# CNC.net
KiCad netlist of a schematic drawn in EAGLE
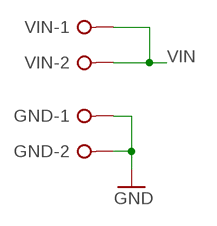
[diagram p0: schematic, sheet 1, part 1 of 2]
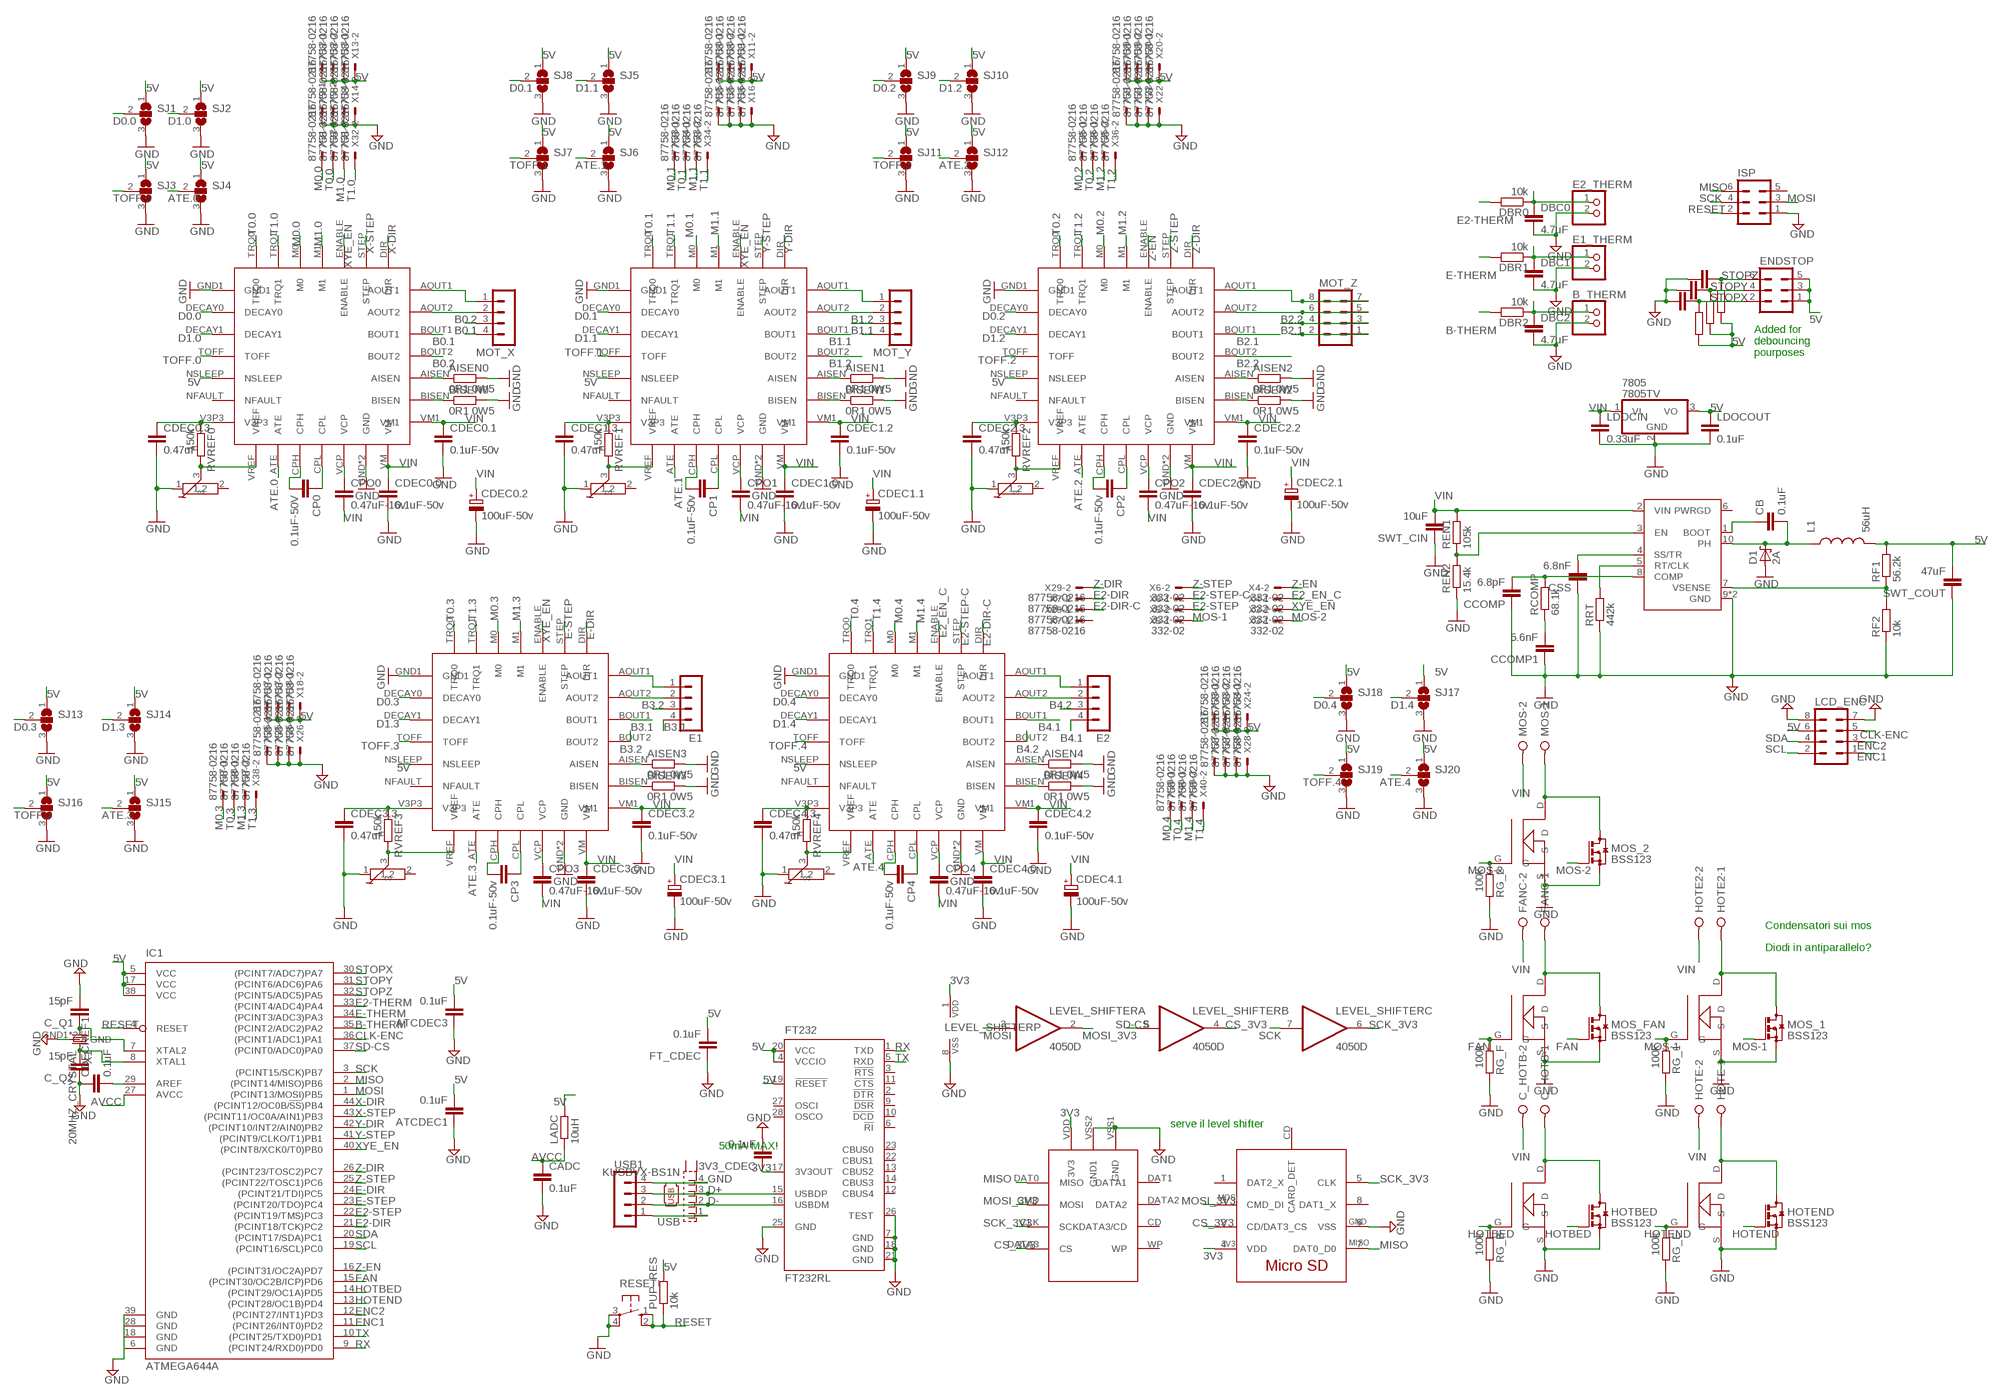
[diagram p1: schematic, sheet 1, part 2 of 2]

(export (version "E")
  (design (tool "Eeschema 10.0.6"))
  (components
    (comp (ref "3V3_CDEC")
      (value "0.1uF")
      (footprint "eagle-import:C0603")
      (libsource (lib "eagle-import") (part "C-EUC0603"))
    )
    (comp (ref "7805")
      (value "7805TV")
      (footprint "eagle-import:TO220V")
      (libsource (lib "eagle-import") (part "78TV05"))
    )
    (comp (ref "AISEN0")
      (value "0R1 0W5")
      (footprint "eagle-import:R0805")
      (libsource (lib "eagle-import") (part "R-EU_R0805"))
    )
    (comp (ref "AISEN1")
      (value "0R1 0W5")
      (footprint "eagle-import:R0805")
      (libsource (lib "eagle-import") (part "R-EU_R0805"))
    )
    (comp (ref "AISEN2")
      (value "0R1 0W5")
      (footprint "eagle-import:R0805")
      (libsource (lib "eagle-import") (part "R-EU_R0805"))
    )
    (comp (ref "AISEN3")
      (value "0R1 0W5")
      (footprint "eagle-import:R0805")
      (libsource (lib "eagle-import") (part "R-EU_R0805"))
    )
    (comp (ref "AISEN4")
      (value "0R1 0W5")
      (footprint "eagle-import:R0805")
      (libsource (lib "eagle-import") (part "R-EU_R0805"))
    )
    (comp (ref "ATCDEC1")
      (value "0.1uF")
      (footprint "eagle-import:C0603")
      (libsource (lib "eagle-import") (part "C-EUC0603"))
    )
    (comp (ref "ATCDEC3")
      (value "0.1uF")
      (footprint "eagle-import:C0603")
      (libsource (lib "eagle-import") (part "C-EUC0603"))
    )
    (comp (ref "BISEN0")
      (value "0R1 0W5")
      (footprint "eagle-import:R0805")
      (libsource (lib "eagle-import") (part "R-EU_R0805"))
    )
    (comp (ref "BISEN1")
      (value "0R1 0W5")
      (footprint "eagle-import:R0805")
      (libsource (lib "eagle-import") (part "R-EU_R0805"))
    )
    (comp (ref "BISEN2")
      (value "0R1 0W5")
      (footprint "eagle-import:R0805")
      (libsource (lib "eagle-import") (part "R-EU_R0805"))
    )
    (comp (ref "BISEN3")
      (value "0R1 0W5")
      (footprint "eagle-import:R0805")
      (libsource (lib "eagle-import") (part "R-EU_R0805"))
    )
    (comp (ref "BISEN4")
      (value "0R1 0W5")
      (footprint "eagle-import:R0805")
      (libsource (lib "eagle-import") (part "R-EU_R0805"))
    )
    (comp (ref "B_THERM")
      (value "PINHD-1X2")
      (footprint "eagle-import:1X02")
      (libsource (lib "eagle-import") (part "PINHD-1X2"))
    )
    (comp (ref "CADC")
      (value "0.1uF")
      (footprint "eagle-import:C0603")
      (libsource (lib "eagle-import") (part "C-EUC0603"))
    )
    (comp (ref "CB")
      (value "0.1uF")
      (footprint "eagle-import:C0603")
      (libsource (lib "eagle-import") (part "C-EUC0603"))
    )
    (comp (ref "CCOMP")
      (value "6.8pF")
      (footprint "eagle-import:C0603")
      (libsource (lib "eagle-import") (part "C-EUC0603"))
    )
    (comp (ref "CCOMP1")
      (value "5.6nF")
      (footprint "eagle-import:C0603")
      (libsource (lib "eagle-import") (part "C-EUC0603"))
    )
    (comp (ref "CDEC0.0")
      (value "0.1uF-50v")
      (footprint "eagle-import:C0603")
      (libsource (lib "eagle-import") (part "C-EUC0603"))
    )
    (comp (ref "CDEC0.1")
      (value "0.1uF-50v")
      (footprint "eagle-import:C0603")
      (libsource (lib "eagle-import") (part "C-EUC0603"))
    )
    (comp (ref "CDEC0.2")
      (value "100uF-50v")
      (footprint "eagle-import:E3,5-8")
      (libsource (lib "eagle-import") (part "CPOL-EUE3.5-8"))
    )
    (comp (ref "CDEC0.3")
      (value "0.47uF")
      (footprint "eagle-import:C0603")
      (libsource (lib "eagle-import") (part "C-EUC0603"))
    )
    (comp (ref "CDEC1.0")
      (value "0.1uF-50v")
      (footprint "eagle-import:C0603")
      (libsource (lib "eagle-import") (part "C-EUC0603"))
    )
    (comp (ref "CDEC1.1")
      (value "100uF-50v")
      (footprint "eagle-import:E3,5-8")
      (libsource (lib "eagle-import") (part "CPOL-EUE3.5-8"))
    )
    (comp (ref "CDEC1.2")
      (value "0.1uF-50v")
      (footprint "eagle-import:C0603")
      (libsource (lib "eagle-import") (part "C-EUC0603"))
    )
    (comp (ref "CDEC1.3")
      (value "0.47uF")
      (footprint "eagle-import:C0603")
      (libsource (lib "eagle-import") (part "C-EUC0603"))
    )
    (comp (ref "CDEC2.0")
      (value "0.1uF-50v")
      (footprint "eagle-import:C0603")
      (libsource (lib "eagle-import") (part "C-EUC0603"))
    )
    (comp (ref "CDEC2.1")
      (value "100uF-50v")
      (footprint "eagle-import:E3,5-8")
      (libsource (lib "eagle-import") (part "CPOL-EUE3.5-8"))
    )
    (comp (ref "CDEC2.2")
      (value "0.1uF-50v")
      (footprint "eagle-import:C0603")
      (libsource (lib "eagle-import") (part "C-EUC0603"))
    )
    (comp (ref "CDEC2.3")
      (value "0.47uF")
      (footprint "eagle-import:C0603")
      (libsource (lib "eagle-import") (part "C-EUC0603"))
    )
    (comp (ref "CDEC3.0")
      (value "0.1uF-50v")
      (footprint "eagle-import:C0603")
      (libsource (lib "eagle-import") (part "C-EUC0603"))
    )
    (comp (ref "CDEC3.1")
      (value "100uF-50v")
      (footprint "eagle-import:E3,5-8")
      (libsource (lib "eagle-import") (part "CPOL-EUE3.5-8"))
    )
    (comp (ref "CDEC3.2")
      (value "0.1uF-50v")
      (footprint "eagle-import:C0603")
      (libsource (lib "eagle-import") (part "C-EUC0603"))
    )
    (comp (ref "CDEC3.3")
      (value "0.47uF")
      (footprint "eagle-import:C0603")
      (libsource (lib "eagle-import") (part "C-EUC0603"))
    )
    (comp (ref "CDEC4.0")
      (value "0.1uF-50v")
      (footprint "eagle-import:C0603")
      (libsource (lib "eagle-import") (part "C-EUC0603"))
    )
    (comp (ref "CDEC4.1")
      (value "100uF-50v")
      (footprint "eagle-import:E3,5-8")
      (libsource (lib "eagle-import") (part "CPOL-EUE3.5-8"))
    )
    (comp (ref "CDEC4.2")
      (value "0.1uF-50v")
      (footprint "eagle-import:C0603")
      (libsource (lib "eagle-import") (part "C-EUC0603"))
    )
    (comp (ref "CDEC4.3")
      (value "0.47uF")
      (footprint "eagle-import:C0603")
      (libsource (lib "eagle-import") (part "C-EUC0603"))
    )
    (comp (ref "CDECREF1")
      (value "0.1uF")
      (footprint "eagle-import:C0603")
      (libsource (lib "eagle-import") (part "C-EUC0603"))
    )
    (comp (ref "CP0")
      (value "0.1uF-50V")
      (footprint "eagle-import:C0603")
      (libsource (lib "eagle-import") (part "C-EUC0603"))
    )
    (comp (ref "CP1")
      (value "0.1uF-50v")
      (footprint "eagle-import:C0603")
      (libsource (lib "eagle-import") (part "C-EUC0603"))
    )
    (comp (ref "CP2")
      (value "0.1uF-50v")
      (footprint "eagle-import:C0603")
      (libsource (lib "eagle-import") (part "C-EUC0603"))
    )
    (comp (ref "CP3")
      (value "0.1uF-50v")
      (footprint "eagle-import:C0603")
      (libsource (lib "eagle-import") (part "C-EUC0603"))
    )
    (comp (ref "CP4")
      (value "0.1uF-50v")
      (footprint "eagle-import:C0603")
      (libsource (lib "eagle-import") (part "C-EUC0603"))
    )
    (comp (ref "CPO0")
      (value "0.47uF-16v")
      (footprint "eagle-import:C0603")
      (libsource (lib "eagle-import") (part "C-EUC0603"))
    )
    (comp (ref "CPO1")
      (value "0.47uF-16v")
      (footprint "eagle-import:C0603")
      (libsource (lib "eagle-import") (part "C-EUC0603"))
    )
    (comp (ref "CPO2")
      (value "0.47uF-16v")
      (footprint "eagle-import:C0603")
      (libsource (lib "eagle-import") (part "C-EUC0603"))
    )
    (comp (ref "CPO3")
      (value "0.47uF-16v")
      (footprint "eagle-import:C0603")
      (libsource (lib "eagle-import") (part "C-EUC0603"))
    )
    (comp (ref "CPO4")
      (value "0.47uF-16v")
      (footprint "eagle-import:C0603")
      (libsource (lib "eagle-import") (part "C-EUC0603"))
    )
    (comp (ref "CSS")
      (value "6.8nF")
      (footprint "eagle-import:C0603")
      (libsource (lib "eagle-import") (part "C-EUC0603"))
    )
    (comp (ref "C_HOTB")
      (value "W237-02P")
      (footprint "eagle-import:W237-132")
      (libsource (lib "eagle-import") (part "W237-02P"))
    )
    (comp (ref "C_Q1")
      (value "15pF")
      (footprint "eagle-import:C0603")
      (libsource (lib "eagle-import") (part "C-EUC0603"))
    )
    (comp (ref "C_Q2")
      (value "15pF")
      (footprint "eagle-import:C0603")
      (libsource (lib "eagle-import") (part "C-EUC0603"))
    )
    (comp (ref "D1")
      (value "2A")
      (footprint "eagle-import:SMB")
      (libsource (lib "eagle-import") (part "MBRS130LT3"))
    )
    (comp (ref "DBC0")
      (value "4.7uF")
      (footprint "eagle-import:C0603")
      (libsource (lib "eagle-import") (part "C-EUC0603"))
    )
    (comp (ref "DBC1")
      (value "4.7uF")
      (footprint "eagle-import:C0603")
      (libsource (lib "eagle-import") (part "C-EUC0603"))
    )
    (comp (ref "DBC2")
      (value "4.7uF")
      (footprint "eagle-import:C0603")
      (libsource (lib "eagle-import") (part "C-EUC0603"))
    )
    (comp (ref "DBC3")
      (value "0.1uF")
      (footprint "eagle-import:C0603")
      (libsource (lib "eagle-import") (part "C-EUC0603"))
    )
    (comp (ref "DBC4")
      (value "0.1uF")
      (footprint "eagle-import:C0603")
      (libsource (lib "eagle-import") (part "C-EUC0603"))
    )
    (comp (ref "DBC5")
      (value "0.1uF")
      (footprint "eagle-import:C0603")
      (libsource (lib "eagle-import") (part "C-EUC0603"))
    )
    (comp (ref "DBR0")
      (value "10k")
      (footprint "eagle-import:R0603")
      (libsource (lib "eagle-import") (part "R-EU_R0603"))
    )
    (comp (ref "DBR1")
      (value "10k")
      (footprint "eagle-import:R0603")
      (libsource (lib "eagle-import") (part "R-EU_R0603"))
    )
    (comp (ref "DBR2")
      (value "10k")
      (footprint "eagle-import:R0603")
      (libsource (lib "eagle-import") (part "R-EU_R0603"))
    )
    (comp (ref "DBR3")
      (value "10k")
      (footprint "eagle-import:R0603")
      (libsource (lib "eagle-import") (part "R-EU_R0603"))
    )
    (comp (ref "DBR4")
      (value "10k")
      (footprint "eagle-import:R0603")
      (libsource (lib "eagle-import") (part "R-EU_R0603"))
    )
    (comp (ref "DBR5")
      (value "10k")
      (footprint "eagle-import:R0603")
      (libsource (lib "eagle-import") (part "R-EU_R0603"))
    )
    (comp (ref "E1")
      (value "MA04-1")
      (footprint "eagle-import:MA04-1")
      (libsource (lib "eagle-import") (part "MA04-1"))
    )
    (comp (ref "E1_THERM")
      (value "PINHD-1X2")
      (footprint "eagle-import:1X02")
      (libsource (lib "eagle-import") (part "PINHD-1X2"))
    )
    (comp (ref "E2")
      (value "MA04-1")
      (footprint "eagle-import:MA04-1")
      (libsource (lib "eagle-import") (part "MA04-1"))
    )
    (comp (ref "E2_THERM")
      (value "PINHD-1X2")
      (footprint "eagle-import:1X02")
      (libsource (lib "eagle-import") (part "PINHD-1X2"))
    )
    (comp (ref "ENDSTOP")
      (value "MA03-2")
      (footprint "eagle-import:MA03-2")
      (libsource (lib "eagle-import") (part "MA03-2"))
    )
    (comp (ref "EXT_1")
      (value "DRV8880")
      (footprint "eagle-import:HTSSOP")
      (libsource (lib "eagle-import") (part "DRV8880"))
    )
    (comp (ref "EXT_2")
      (value "DRV8880")
      (footprint "eagle-import:HTSSOP")
      (libsource (lib "eagle-import") (part "DRV8880"))
    )
    (comp (ref "FANC")
      (value "W237-02P")
      (footprint "eagle-import:W237-132")
      (libsource (lib "eagle-import") (part "W237-02P"))
    )
    (comp (ref "FT232")
      (value "FT232RL")
      (footprint "eagle-import:SSOP28")
      (libsource (lib "eagle-import") (part "FT232RL"))
    )
    (comp (ref "FT_CDEC")
      (value "0.1uF")
      (footprint "eagle-import:C0603")
      (libsource (lib "eagle-import") (part "C-EUC0603"))
    )
    (comp (ref "GND")
      (value "W237-02P")
      (footprint "eagle-import:W237-132")
      (libsource (lib "eagle-import") (part "W237-02P"))
    )
    (comp (ref "HOTBED")
      (value "BSS123")
      (footprint "eagle-import:SOT23")
      (libsource (lib "eagle-import") (part "BSS123"))
    )
    (comp (ref "HOTBED1")
      (value "POWER_MOSFET")
      (footprint "eagle-import:D2PAK")
      (libsource (lib "eagle-import") (part "POWER_MOSFET"))
    )
    (comp (ref "HOTE")
      (value "W237-02P")
      (footprint "eagle-import:W237-132")
      (libsource (lib "eagle-import") (part "W237-02P"))
    )
    (comp (ref "HOTE2")
      (value "W237-02P")
      (footprint "eagle-import:W237-132")
      (libsource (lib "eagle-import") (part "W237-02P"))
    )
    (comp (ref "HOTEND")
      (value "BSS123")
      (footprint "eagle-import:SOT23")
      (libsource (lib "eagle-import") (part "BSS123"))
    )
    (comp (ref "HOTEND1")
      (value "POWER_MOSFET")
      (footprint "eagle-import:D2PAK")
      (libsource (lib "eagle-import") (part "POWER_MOSFET"))
    )
    (comp (ref "IC1")
      (value "ATMEGA644A")
      (footprint "eagle-import:TQFP44")
      (fields (field (name "MPN") "ATMEGA644PV-10AU"))
      (libsource (lib "eagle-import") (part "ATMEGA644A"))
    )
    (comp (ref "ISP")
      (value "MA03-2")
      (footprint "eagle-import:MA03-2")
      (libsource (lib "eagle-import") (part "MA03-2"))
    )
    (comp (ref "L1")
      (value "56uH")
      (footprint "eagle-import:INDUCTOR")
      (libsource (lib "eagle-import") (part "INDUCTOR"))
    )
    (comp (ref "LADC")
      (value "10uH")
      (footprint "eagle-import:R0603")
      (libsource (lib "eagle-import") (part "R-EU_R0603"))
    )
    (comp (ref "LCD_ENC")
      (value "MA04-2")
      (footprint "eagle-import:MA04-2")
      (libsource (lib "eagle-import") (part "MA04-2"))
    )
    (comp (ref "LDOCIN")
      (value "0.33uF")
      (footprint "eagle-import:C0603")
      (libsource (lib "eagle-import") (part "C-EUC0603"))
    )
    (comp (ref "LDOCOUT")
      (value "0.1uF")
      (footprint "eagle-import:C0603")
      (libsource (lib "eagle-import") (part "C-EUC0603"))
    )
    (comp (ref "LEVEL_SHIFTER")
      (value "4050D")
      (footprint "eagle-import:SO16")
      (libsource (lib "eagle-import") (part "4050D"))
    )
    (comp (ref "MOS")
      (value "W237-02P")
      (footprint "eagle-import:W237-132")
      (libsource (lib "eagle-import") (part "W237-02P"))
    )
    (comp (ref "MOS11")
      (value "POWER_MOSFET")
      (footprint "eagle-import:D2PAK")
      (libsource (lib "eagle-import") (part "POWER_MOSFET"))
    )
    (comp (ref "MOS22")
      (value "POWER_MOSFET")
      (footprint "eagle-import:D2PAK")
      (libsource (lib "eagle-import") (part "POWER_MOSFET"))
    )
    (comp (ref "MOS_1")
      (value "BSS123")
      (footprint "eagle-import:SOT23")
      (libsource (lib "eagle-import") (part "BSS123"))
    )
    (comp (ref "MOS_2")
      (value "BSS123")
      (footprint "eagle-import:SOT23")
      (libsource (lib "eagle-import") (part "BSS123"))
    )
    (comp (ref "MOS_FAN")
      (value "BSS123")
      (footprint "eagle-import:SOT23")
      (libsource (lib "eagle-import") (part "BSS123"))
    )
    (comp (ref "MOS_FAN1")
      (value "POWER_MOSFET")
      (footprint "eagle-import:D2PAK")
      (libsource (lib "eagle-import") (part "POWER_MOSFET"))
    )
    (comp (ref "MOT_X")
      (value "MA04-1")
      (footprint "eagle-import:MA04-1")
      (libsource (lib "eagle-import") (part "MA04-1"))
    )
    (comp (ref "MOT_Y")
      (value "MA04-1")
      (footprint "eagle-import:MA04-1")
      (libsource (lib "eagle-import") (part "MA04-1"))
    )
    (comp (ref "MOT_Z")
      (value "MA04-2")
      (footprint "eagle-import:MA04-2")
      (libsource (lib "eagle-import") (part "MA04-2"))
    )
    (comp (ref "PUP_RES")
      (value "10k")
      (footprint "eagle-import:R0603")
      (libsource (lib "eagle-import") (part "R-EU_R0603"))
    )
    (comp (ref "RCOMP")
      (value "68.1k")
      (footprint "eagle-import:R0603")
      (libsource (lib "eagle-import") (part "R-EU_R0603"))
    )
    (comp (ref "REN1")
      (value "105k")
      (footprint "eagle-import:R0603")
      (libsource (lib "eagle-import") (part "R-EU_R0603"))
    )
    (comp (ref "REN2")
      (value "15.4k")
      (footprint "eagle-import:R0603")
      (libsource (lib "eagle-import") (part "R-EU_R0603"))
    )
    (comp (ref "RESET")
      (value "10-XX")
      (footprint "eagle-import:B3F-10XX")
      (fields (field (name "MPN") "B3F-1000"))
      (libsource (lib "eagle-import") (part "10-XX"))
    )
    (comp (ref "RF1")
      (value "56.2k")
      (footprint "eagle-import:R0603")
      (libsource (lib "eagle-import") (part "R-EU_R0603"))
    )
    (comp (ref "RF2")
      (value "10k")
      (footprint "eagle-import:R0603")
      (libsource (lib "eagle-import") (part "R-EU_R0603"))
    )
    (comp (ref "RG_1")
      (value "100k")
      (footprint "eagle-import:R0603")
      (libsource (lib "eagle-import") (part "R-EU_R0603"))
    )
    (comp (ref "RG_2")
      (value "100k")
      (footprint "eagle-import:R0603")
      (libsource (lib "eagle-import") (part "R-EU_R0603"))
    )
    (comp (ref "RG_B")
      (value "100k")
      (footprint "eagle-import:R0603")
      (libsource (lib "eagle-import") (part "R-EU_R0603"))
    )
    (comp (ref "RG_E")
      (value "100k")
      (footprint "eagle-import:R0603")
      (libsource (lib "eagle-import") (part "R-EU_R0603"))
    )
    (comp (ref "RG_F")
      (value "100k")
      (footprint "eagle-import:R0603")
      (libsource (lib "eagle-import") (part "R-EU_R0603"))
    )
    (comp (ref "RRT")
      (value "442k")
      (footprint "eagle-import:R0603")
      (libsource (lib "eagle-import") (part "R-EU_R0603"))
    )
    (comp (ref "RVREF0")
      (value "150k")
      (footprint "eagle-import:R0603")
      (libsource (lib "eagle-import") (part "R-EU_R0603"))
    )
    (comp (ref "RVREF1")
      (value "150k")
      (footprint "eagle-import:R0603")
      (libsource (lib "eagle-import") (part "R-EU_R0603"))
    )
    (comp (ref "RVREF2")
      (value "150k")
      (footprint "eagle-import:R0603")
      (libsource (lib "eagle-import") (part "R-EU_R0603"))
    )
    (comp (ref "RVREF3")
      (value "150k")
      (footprint "eagle-import:R0603")
      (libsource (lib "eagle-import") (part "R-EU_R0603"))
    )
    (comp (ref "RVREF4")
      (value "150k")
      (footprint "eagle-import:R0603")
      (libsource (lib "eagle-import") (part "R-EU_R0603"))
    )
    (comp (ref "SD")
      (value "SD_CARD")
      (footprint "eagle-import:SD_CARD")
      (libsource (lib "eagle-import") (part "SD_CARD"))
    )
    (comp (ref "SJ1")
      (value "SJ2W")
      (footprint "eagle-import:SJ_2")
      (libsource (lib "eagle-import") (part "SJ2W"))
    )
    (comp (ref "SJ2")
      (value "SJ2W")
      (footprint "eagle-import:SJ_2")
      (libsource (lib "eagle-import") (part "SJ2W"))
    )
    (comp (ref "SJ3")
      (value "SJ2W")
      (footprint "eagle-import:SJ_2")
      (libsource (lib "eagle-import") (part "SJ2W"))
    )
    (comp (ref "SJ4")
      (value "SJ2W")
      (footprint "eagle-import:SJ_2")
      (libsource (lib "eagle-import") (part "SJ2W"))
    )
    (comp (ref "SJ5")
      (value "SJ2W")
      (footprint "eagle-import:SJ_2")
      (libsource (lib "eagle-import") (part "SJ2W"))
    )
    (comp (ref "SJ6")
      (value "SJ2W")
      (footprint "eagle-import:SJ_2")
      (libsource (lib "eagle-import") (part "SJ2W"))
    )
    (comp (ref "SJ7")
      (value "SJ2W")
      (footprint "eagle-import:SJ_2")
      (libsource (lib "eagle-import") (part "SJ2W"))
    )
    (comp (ref "SJ8")
      (value "SJ2W")
      (footprint "eagle-import:SJ_2")
      (libsource (lib "eagle-import") (part "SJ2W"))
    )
    (comp (ref "SJ9")
      (value "SJ2W")
      (footprint "eagle-import:SJ_2")
      (libsource (lib "eagle-import") (part "SJ2W"))
    )
    (comp (ref "SJ10")
      (value "SJ2W")
      (footprint "eagle-import:SJ_2")
      (libsource (lib "eagle-import") (part "SJ2W"))
    )
    (comp (ref "SJ11")
      (value "SJ2W")
      (footprint "eagle-import:SJ_2")
      (libsource (lib "eagle-import") (part "SJ2W"))
    )
    (comp (ref "SJ12")
      (value "SJ2W")
      (footprint "eagle-import:SJ_2")
      (libsource (lib "eagle-import") (part "SJ2W"))
    )
    (comp (ref "SJ13")
      (value "SJ2W")
      (footprint "eagle-import:SJ_2")
      (libsource (lib "eagle-import") (part "SJ2W"))
    )
    (comp (ref "SJ14")
      (value "SJ2W")
      (footprint "eagle-import:SJ_2")
      (libsource (lib "eagle-import") (part "SJ2W"))
    )
    (comp (ref "SJ15")
      (value "SJ2W")
      (footprint "eagle-import:SJ_2")
      (libsource (lib "eagle-import") (part "SJ2W"))
    )
    (comp (ref "SJ16")
      (value "SJ2W")
      (footprint "eagle-import:SJ_2")
      (libsource (lib "eagle-import") (part "SJ2W"))
    )
    (comp (ref "SJ17")
      (value "SJ2W")
      (footprint "eagle-import:SJ_2")
      (libsource (lib "eagle-import") (part "SJ2W"))
    )
    (comp (ref "SJ18")
      (value "SJ2W")
      (footprint "eagle-import:SJ_2")
      (libsource (lib "eagle-import") (part "SJ2W"))
    )
    (comp (ref "SJ19")
      (value "SJ2W")
      (footprint "eagle-import:SJ_2")
      (libsource (lib "eagle-import") (part "SJ2W"))
    )
    (comp (ref "SJ20")
      (value "SJ2W")
      (footprint "eagle-import:SJ_2")
      (libsource (lib "eagle-import") (part "SJ2W"))
    )
    (comp (ref "SUPPLY")
      (value "TPS54160")
      (footprint "eagle-import:MSOP")
      (libsource (lib "eagle-import") (part "TPS54160"))
    )
    (comp (ref "SWT_CIN")
      (value "10uF")
      (footprint "eagle-import:C0603")
      (libsource (lib "eagle-import") (part "C-EUC0603"))
    )
    (comp (ref "SWT_COUT")
      (value "47uF")
      (footprint "eagle-import:C0603")
      (libsource (lib "eagle-import") (part "C-EUC0603"))
    )
    (comp (ref "T0")
      (value "100k")
      (footprint "eagle-import:TRIMMER")
      (libsource (lib "eagle-import") (part "TRIMMER"))
    )
    (comp (ref "T1")
      (value "TRIMMER")
      (footprint "eagle-import:TRIMMER")
      (libsource (lib "eagle-import") (part "TRIMMER"))
    )
    (comp (ref "T2")
      (value "TRIMMER")
      (footprint "eagle-import:TRIMMER")
      (libsource (lib "eagle-import") (part "TRIMMER"))
    )
    (comp (ref "T3")
      (value "TRIMMER")
      (footprint "eagle-import:TRIMMER")
      (libsource (lib "eagle-import") (part "TRIMMER"))
    )
    (comp (ref "T4")
      (value "TRIMMER")
      (footprint "eagle-import:TRIMMER")
      (libsource (lib "eagle-import") (part "TRIMMER"))
    )
    (comp (ref "USB")
      (value "KUSBVX-BS1N")
      (footprint "eagle-import:KUSBVX-BS1N")
      (libsource (lib "eagle-import") (part "KUSBVX-BS1N"))
    )
    (comp (ref "USB1")
      (value "MA04-1")
      (footprint "eagle-import:MA04-1")
      (libsource (lib "eagle-import") (part "MA04-1"))
    )
    (comp (ref "USD")
      (value "MICRO-SD")
      (footprint "eagle-import:MICRO-SD")
      (libsource (lib "eagle-import") (part "MICRO-SD"))
    )
    (comp (ref "VIN")
      (value "W237-02P")
      (footprint "eagle-import:W237-132")
      (libsource (lib "eagle-import") (part "W237-02P"))
    )
    (comp (ref "X1")
      (value "20MHZ_CRYSTAL")
      (footprint "eagle-import:SMD-3225_4P")
      (libsource (lib "eagle-import") (part "20MHZ_CRYSTAL"))
    )
    (comp (ref "X3")
      (value "332-02")
      (footprint "eagle-import:332-02")
      (libsource (lib "eagle-import") (part "332-02"))
    )
    (comp (ref "X4")
      (value "332-02")
      (footprint "eagle-import:332-02")
      (libsource (lib "eagle-import") (part "332-02"))
    )
    (comp (ref "X5")
      (value "332-02")
      (footprint "eagle-import:332-02")
      (libsource (lib "eagle-import") (part "332-02"))
    )
    (comp (ref "X6")
      (value "332-02")
      (footprint "eagle-import:332-02")
      (libsource (lib "eagle-import") (part "332-02"))
    )
    (comp (ref "X7")
      (value "87758-0216")
      (footprint "eagle-import:87758-0216")
      (fields (field (name "MF") "MOLEX"))
      (libsource (lib "eagle-import") (part "87758-0216"))
    )
    (comp (ref "X9")
      (value "87758-0216")
      (footprint "eagle-import:87758-0216")
      (fields (field (name "MF") "MOLEX"))
      (libsource (lib "eagle-import") (part "87758-0216"))
    )
    (comp (ref "X10")
      (value "87758-0216")
      (footprint "eagle-import:87758-0216")
      (fields (field (name "MF") "MOLEX"))
      (libsource (lib "eagle-import") (part "87758-0216"))
    )
    (comp (ref "X11")
      (value "87758-0216")
      (footprint "eagle-import:87758-0216")
      (fields (field (name "MF") "MOLEX"))
      (libsource (lib "eagle-import") (part "87758-0216"))
    )
    (comp (ref "X12")
      (value "87758-0216")
      (footprint "eagle-import:87758-0216")
      (fields (field (name "MF") "MOLEX"))
      (libsource (lib "eagle-import") (part "87758-0216"))
    )
    (comp (ref "X13")
      (value "87758-0216")
      (footprint "eagle-import:87758-0216")
      (fields (field (name "MF") "MOLEX"))
      (libsource (lib "eagle-import") (part "87758-0216"))
    )
    (comp (ref "X14")
      (value "87758-0216")
      (footprint "eagle-import:87758-0216")
      (fields (field (name "MF") "MOLEX"))
      (libsource (lib "eagle-import") (part "87758-0216"))
    )
    (comp (ref "X15")
      (value "87758-0216")
      (footprint "eagle-import:87758-0216")
      (fields (field (name "MF") "MOLEX"))
      (libsource (lib "eagle-import") (part "87758-0216"))
    )
    (comp (ref "X16")
      (value "87758-0216")
      (footprint "eagle-import:87758-0216")
      (fields (field (name "MF") "MOLEX"))
      (libsource (lib "eagle-import") (part "87758-0216"))
    )
    (comp (ref "X17")
      (value "87758-0216")
      (footprint "eagle-import:87758-0216")
      (fields (field (name "MF") "MOLEX"))
      (libsource (lib "eagle-import") (part "87758-0216"))
    )
    (comp (ref "X18")
      (value "87758-0216")
      (footprint "eagle-import:87758-0216")
      (fields (field (name "MF") "MOLEX"))
      (libsource (lib "eagle-import") (part "87758-0216"))
    )
    (comp (ref "X19")
      (value "87758-0216")
      (footprint "eagle-import:87758-0216")
      (fields (field (name "MF") "MOLEX"))
      (libsource (lib "eagle-import") (part "87758-0216"))
    )
    (comp (ref "X20")
      (value "87758-0216")
      (footprint "eagle-import:87758-0216")
      (fields (field (name "MF") "MOLEX"))
      (libsource (lib "eagle-import") (part "87758-0216"))
    )
    (comp (ref "X21")
      (value "87758-0216")
      (footprint "eagle-import:87758-0216")
      (fields (field (name "MF") "MOLEX"))
      (libsource (lib "eagle-import") (part "87758-0216"))
    )
    (comp (ref "X22")
      (value "87758-0216")
      (footprint "eagle-import:87758-0216")
      (fields (field (name "MF") "MOLEX"))
      (libsource (lib "eagle-import") (part "87758-0216"))
    )
    (comp (ref "X23")
      (value "87758-0216")
      (footprint "eagle-import:87758-0216")
      (fields (field (name "MF") "MOLEX"))
      (libsource (lib "eagle-import") (part "87758-0216"))
    )
    (comp (ref "X24")
      (value "87758-0216")
      (footprint "eagle-import:87758-0216")
      (fields (field (name "MF") "MOLEX"))
      (libsource (lib "eagle-import") (part "87758-0216"))
    )
    (comp (ref "X25")
      (value "87758-0216")
      (footprint "eagle-import:87758-0216")
      (fields (field (name "MF") "MOLEX"))
      (libsource (lib "eagle-import") (part "87758-0216"))
    )
    (comp (ref "X26")
      (value "87758-0216")
      (footprint "eagle-import:87758-0216")
      (fields (field (name "MF") "MOLEX"))
      (libsource (lib "eagle-import") (part "87758-0216"))
    )
    (comp (ref "X27")
      (value "87758-0216")
      (footprint "eagle-import:87758-0216")
      (fields (field (name "MF") "MOLEX"))
      (libsource (lib "eagle-import") (part "87758-0216"))
    )
    (comp (ref "X28")
      (value "87758-0216")
      (footprint "eagle-import:87758-0216")
      (fields (field (name "MF") "MOLEX"))
      (libsource (lib "eagle-import") (part "87758-0216"))
    )
    (comp (ref "X29")
      (value "87758-0216")
      (footprint "eagle-import:87758-0216")
      (fields (field (name "MF") "MOLEX"))
      (libsource (lib "eagle-import") (part "87758-0216"))
    )
    (comp (ref "X31")
      (value "87758-0216")
      (footprint "eagle-import:87758-0216")
      (fields (field (name "MF") "MOLEX"))
      (libsource (lib "eagle-import") (part "87758-0216"))
    )
    (comp (ref "X32")
      (value "87758-0216")
      (footprint "eagle-import:87758-0216")
      (fields (field (name "MF") "MOLEX"))
      (libsource (lib "eagle-import") (part "87758-0216"))
    )
    (comp (ref "X33")
      (value "87758-0216")
      (footprint "eagle-import:87758-0216")
      (fields (field (name "MF") "MOLEX"))
      (libsource (lib "eagle-import") (part "87758-0216"))
    )
    (comp (ref "X34")
      (value "87758-0216")
      (footprint "eagle-import:87758-0216")
      (fields (field (name "MF") "MOLEX"))
      (libsource (lib "eagle-import") (part "87758-0216"))
    )
    (comp (ref "X35")
      (value "87758-0216")
      (footprint "eagle-import:87758-0216")
      (fields (field (name "MF") "MOLEX"))
      (libsource (lib "eagle-import") (part "87758-0216"))
    )
    (comp (ref "X36")
      (value "87758-0216")
      (footprint "eagle-import:87758-0216")
      (fields (field (name "MF") "MOLEX"))
      (libsource (lib "eagle-import") (part "87758-0216"))
    )
    (comp (ref "X37")
      (value "87758-0216")
      (footprint "eagle-import:87758-0216")
      (fields (field (name "MF") "MOLEX"))
      (libsource (lib "eagle-import") (part "87758-0216"))
    )
    (comp (ref "X38")
      (value "87758-0216")
      (footprint "eagle-import:87758-0216")
      (fields (field (name "MF") "MOLEX"))
      (libsource (lib "eagle-import") (part "87758-0216"))
    )
    (comp (ref "X39")
      (value "87758-0216")
      (footprint "eagle-import:87758-0216")
      (fields (field (name "MF") "MOLEX"))
      (libsource (lib "eagle-import") (part "87758-0216"))
    )
    (comp (ref "X40")
      (value "87758-0216")
      (footprint "eagle-import:87758-0216")
      (fields (field (name "MF") "MOLEX"))
      (libsource (lib "eagle-import") (part "87758-0216"))
    )
    (comp (ref "X_AXIS")
      (value "DRV8880")
      (footprint "eagle-import:HTSSOP")
      (libsource (lib "eagle-import") (part "DRV8880"))
    )
    (comp (ref "Y-AXIS")
      (value "DRV8880")
      (footprint "eagle-import:HTSSOP")
      (libsource (lib "eagle-import") (part "DRV8880"))
    )
    (comp (ref "Z_AXIS")
      (value "DRV8880")
      (footprint "eagle-import:HTSSOP")
      (libsource (lib "eagle-import") (part "DRV8880"))
    )
  )
  (nets
    (net (code "1") (name "/3V3") (class "Default")
      (node (ref "3V3_CDEC") (pin "1") (pinfunction "1_1") (pintype "passive"))
      (node (ref "FT232") (pin "17") (pinfunction "3V3OUT_17") (pintype "output"))
      (node (ref "LEVEL_SHIFTER") (pin "1") (pinfunction "VDD_1") (pintype "power_in"))
      (node (ref "SD") (pin "VDD") (pinfunction "3V3_VDD") (pintype "bidirectional"))
      (node (ref "USD") (pin "4") (pinfunction "VDD_4") (pintype "bidirectional"))
    )
    (net (code "2") (name "/5V") (class "Default")
      (node (ref "7805") (pin "3") (pinfunction "VO_3") (pintype "passive"))
      (node (ref "ATCDEC1") (pin "2") (pinfunction "2_2") (pintype "passive"))
      (node (ref "ATCDEC3") (pin "2") (pinfunction "2_2") (pintype "passive"))
      (node (ref "DBR3") (pin "2") (pinfunction "2_2") (pintype "passive"))
      (node (ref "DBR4") (pin "2") (pinfunction "2_2") (pintype "passive"))
      (node (ref "DBR5") (pin "2") (pinfunction "2_2") (pintype "passive"))
      (node (ref "ENDSTOP") (pin "1") (pinfunction "1_1") (pintype "passive"))
      (node (ref "ENDSTOP") (pin "3") (pinfunction "3_3") (pintype "passive"))
      (node (ref "ENDSTOP") (pin "5") (pinfunction "5_5") (pintype "passive"))
      (node (ref "EXT_1") (pin "NSLEEP") (pinfunction "NSLEEP_NSLEEP") (pintype "bidirectional"))
      (node (ref "EXT_2") (pin "NSLEEP") (pinfunction "NSLEEP_NSLEEP") (pintype "bidirectional"))
      (node (ref "FT232") (pin "19") (pinfunction "~{RESET}_19") (pintype "input"))
      (node (ref "FT232") (pin "20") (pinfunction "VCC_20") (pintype "power_in"))
      (node (ref "FT232") (pin "4") (pinfunction "VCCIO_4") (pintype "power_in"))
      (node (ref "FT_CDEC") (pin "2") (pinfunction "2_2") (pintype "passive"))
      (node (ref "IC1") (pin "17") (pinfunction "VCC_17") (pintype "power_in"))
      (node (ref "IC1") (pin "38") (pinfunction "VCC_38") (pintype "power_in"))
      (node (ref "IC1") (pin "5") (pinfunction "VCC_5") (pintype "power_in"))
      (node (ref "L1") (pin "2") (pinfunction "2_2") (pintype "passive"))
      (node (ref "LADC") (pin "2") (pinfunction "2_2") (pintype "passive"))
      (node (ref "LCD_ENC") (pin "6") (pinfunction "6_6") (pintype "passive"))
      (node (ref "LDOCOUT") (pin "1") (pinfunction "1_1") (pintype "passive"))
      (node (ref "PUP_RES") (pin "2") (pinfunction "2_2") (pintype "passive"))
      (node (ref "RF1") (pin "2") (pinfunction "2_2") (pintype "passive"))
      (node (ref "SJ1") (pin "1") (pinfunction "1_1") (pintype "passive"))
      (node (ref "SJ10") (pin "1") (pinfunction "1_1") (pintype "passive"))
      (node (ref "SJ11") (pin "1") (pinfunction "1_1") (pintype "passive"))
      (node (ref "SJ12") (pin "1") (pinfunction "1_1") (pintype "passive"))
      (node (ref "SJ13") (pin "1") (pinfunction "1_1") (pintype "passive"))
      (node (ref "SJ14") (pin "1") (pinfunction "1_1") (pintype "passive"))
      (node (ref "SJ15") (pin "1") (pinfunction "1_1") (pintype "passive"))
      (node (ref "SJ16") (pin "1") (pinfunction "1_1") (pintype "passive"))
      (node (ref "SJ17") (pin "1") (pinfunction "1_1") (pintype "passive"))
      (node (ref "SJ18") (pin "1") (pinfunction "1_1") (pintype "passive"))
      (node (ref "SJ19") (pin "1") (pinfunction "1_1") (pintype "passive"))
      (node (ref "SJ2") (pin "1") (pinfunction "1_1") (pintype "passive"))
      (node (ref "SJ20") (pin "1") (pinfunction "1_1") (pintype "passive"))
      (node (ref "SJ3") (pin "1") (pinfunction "1_1") (pintype "passive"))
      (node (ref "SJ4") (pin "1") (pinfunction "1_1") (pintype "passive"))
      (node (ref "SJ5") (pin "1") (pinfunction "1_1") (pintype "passive"))
      (node (ref "SJ6") (pin "1") (pinfunction "1_1") (pintype "passive"))
      (node (ref "SJ7") (pin "1") (pinfunction "1_1") (pintype "passive"))
      (node (ref "SJ8") (pin "1") (pinfunction "1_1") (pintype "passive"))
      (node (ref "SJ9") (pin "1") (pinfunction "1_1") (pintype "passive"))
      (node (ref "SWT_COUT") (pin "2") (pinfunction "2_2") (pintype "passive"))
      (node (ref "X10") (pin "1") (pinfunction "S_1") (pintype "passive"))
      (node (ref "X10") (pin "2") (pinfunction "S_2") (pintype "passive"))
      (node (ref "X11") (pin "1") (pinfunction "S_1") (pintype "passive"))
      (node (ref "X11") (pin "2") (pinfunction "S_2") (pintype "passive"))
      (node (ref "X12") (pin "1") (pinfunction "S_1") (pintype "passive"))
      (node (ref "X12") (pin "2") (pinfunction "S_2") (pintype "passive"))
      (node (ref "X13") (pin "1") (pinfunction "S_1") (pintype "passive"))
      (node (ref "X13") (pin "2") (pinfunction "S_2") (pintype "passive"))
      (node (ref "X17") (pin "1") (pinfunction "S_1") (pintype "passive"))
      (node (ref "X17") (pin "2") (pinfunction "S_2") (pintype "passive"))
      (node (ref "X18") (pin "1") (pinfunction "S_1") (pintype "passive"))
      (node (ref "X18") (pin "2") (pinfunction "S_2") (pintype "passive"))
      (node (ref "X19") (pin "1") (pinfunction "S_1") (pintype "passive"))
      (node (ref "X19") (pin "2") (pinfunction "S_2") (pintype "passive"))
      (node (ref "X20") (pin "1") (pinfunction "S_1") (pintype "passive"))
      (node (ref "X20") (pin "2") (pinfunction "S_2") (pintype "passive"))
      (node (ref "X23") (pin "1") (pinfunction "S_1") (pintype "passive"))
      (node (ref "X23") (pin "2") (pinfunction "S_2") (pintype "passive"))
      (node (ref "X24") (pin "1") (pinfunction "S_1") (pintype "passive"))
      (node (ref "X24") (pin "2") (pinfunction "S_2") (pintype "passive"))
      (node (ref "X_AXIS") (pin "NSLEEP") (pinfunction "NSLEEP_NSLEEP") (pintype "bidirectional"))
      (node (ref "Y-AXIS") (pin "NSLEEP") (pinfunction "NSLEEP_NSLEEP") (pintype "bidirectional"))
      (node (ref "Z_AXIS") (pin "NSLEEP") (pinfunction "NSLEEP_NSLEEP") (pintype "bidirectional"))
    )
    (net (code "3") (name "/ATE.0") (class "Default")
      (node (ref "SJ4") (pin "2") (pinfunction "2_2") (pintype "passive"))
      (node (ref "X_AXIS") (pin "ATE") (pinfunction "ATE_ATE") (pintype "bidirectional"))
    )
    (net (code "4") (name "/ATE.1") (class "Default")
      (node (ref "SJ6") (pin "2") (pinfunction "2_2") (pintype "passive"))
      (node (ref "Y-AXIS") (pin "ATE") (pinfunction "ATE_ATE") (pintype "bidirectional"))
    )
    (net (code "5") (name "/ATE.2") (class "Default")
      (node (ref "SJ12") (pin "2") (pinfunction "2_2") (pintype "passive"))
      (node (ref "Z_AXIS") (pin "ATE") (pinfunction "ATE_ATE") (pintype "bidirectional"))
    )
    (net (code "6") (name "/ATE.3") (class "Default")
      (node (ref "EXT_1") (pin "ATE") (pinfunction "ATE_ATE") (pintype "bidirectional"))
      (node (ref "SJ15") (pin "2") (pinfunction "2_2") (pintype "passive"))
    )
    (net (code "7") (name "/ATE.4") (class "Default")
      (node (ref "EXT_2") (pin "ATE") (pinfunction "ATE_ATE") (pintype "bidirectional"))
      (node (ref "SJ20") (pin "2") (pinfunction "2_2") (pintype "passive"))
    )
    (net (code "8") (name "/AVCC") (class "Default")
      (node (ref "CADC") (pin "1") (pinfunction "1_1") (pintype "passive"))
      (node (ref "IC1") (pin "27") (pinfunction "AVCC_27") (pintype "power_in"))
      (node (ref "LADC") (pin "1") (pinfunction "1_1") (pintype "passive"))
    )
    (net (code "9") (name "/B-THERM") (class "Default")
      (node (ref "DBR2") (pin "2") (pinfunction "2_2") (pintype "passive"))
      (node (ref "IC1") (pin "35") (pinfunction "(PCINT2/ADC2)PA2_35") (pintype "bidirectional"))
    )
    (net (code "10") (name "/B0.1") (class "Default")
      (node (ref "MOT_X") (pin "4") (pinfunction "4_4") (pintype "passive"))
      (node (ref "X_AXIS") (pin "BOUT1") (pinfunction "BOUT1_BOUT1") (pintype "bidirectional"))
    )
    (net (code "11") (name "/B0.2") (class "Default")
      (node (ref "MOT_X") (pin "3") (pinfunction "3_3") (pintype "passive"))
      (node (ref "X_AXIS") (pin "BOUT2") (pinfunction "BOUT2_BOUT2") (pintype "bidirectional"))
    )
    (net (code "12") (name "/B1.1") (class "Default")
      (node (ref "MOT_Y") (pin "4") (pinfunction "4_4") (pintype "passive"))
      (node (ref "Y-AXIS") (pin "BOUT1") (pinfunction "BOUT1_BOUT1") (pintype "bidirectional"))
    )
    (net (code "13") (name "/B1.2") (class "Default")
      (node (ref "MOT_Y") (pin "3") (pinfunction "3_3") (pintype "passive"))
      (node (ref "Y-AXIS") (pin "BOUT2") (pinfunction "BOUT2_BOUT2") (pintype "bidirectional"))
    )
    (net (code "14") (name "/B2.1") (class "Default")
      (node (ref "MOT_Z") (pin "1") (pinfunction "1_1") (pintype "passive"))
      (node (ref "MOT_Z") (pin "2") (pinfunction "2_2") (pintype "passive"))
      (node (ref "Z_AXIS") (pin "BOUT1") (pinfunction "BOUT1_BOUT1") (pintype "bidirectional"))
    )
    (net (code "15") (name "/B2.2") (class "Default")
      (node (ref "MOT_Z") (pin "3") (pinfunction "3_3") (pintype "passive"))
      (node (ref "MOT_Z") (pin "4") (pinfunction "4_4") (pintype "passive"))
      (node (ref "Z_AXIS") (pin "BOUT2") (pinfunction "BOUT2_BOUT2") (pintype "bidirectional"))
    )
    (net (code "16") (name "/B3.1") (class "Default")
      (node (ref "E1") (pin "4") (pinfunction "4_4") (pintype "passive"))
      (node (ref "EXT_1") (pin "BOUT1") (pinfunction "BOUT1_BOUT1") (pintype "bidirectional"))
    )
    (net (code "17") (name "/B3.2") (class "Default")
      (node (ref "E1") (pin "3") (pinfunction "3_3") (pintype "passive"))
      (node (ref "EXT_1") (pin "BOUT2") (pinfunction "BOUT2_BOUT2") (pintype "bidirectional"))
    )
    (net (code "18") (name "/B4.1") (class "Default")
      (node (ref "E2") (pin "4") (pinfunction "4_4") (pintype "passive"))
      (node (ref "EXT_2") (pin "BOUT1") (pinfunction "BOUT1_BOUT1") (pintype "bidirectional"))
    )
    (net (code "19") (name "/B4.2") (class "Default")
      (node (ref "E2") (pin "3") (pinfunction "3_3") (pintype "passive"))
      (node (ref "EXT_2") (pin "BOUT2") (pinfunction "BOUT2_BOUT2") (pintype "bidirectional"))
    )
    (net (code "20") (name "/CLK-ENC") (class "Default")
      (node (ref "IC1") (pin "36") (pinfunction "(PCINT1/ADC1)PA1_36") (pintype "bidirectional"))
      (node (ref "LCD_ENC") (pin "5") (pinfunction "5_5") (pintype "passive"))
    )
    (net (code "21") (name "/CS_3V3") (class "Default")
      (node (ref "LEVEL_SHIFTER") (pin "4") (pinfunction "O_4") (pintype "output"))
      (node (ref "SD") (pin "DATA3") (pinfunction "CS_DATA3") (pintype "bidirectional"))
      (node (ref "USD") (pin "2") (pinfunction "CD/DAT3_CS_2") (pintype "bidirectional"))
    )
    (net (code "22") (name "/D+") (class "Default")
      (node (ref "FT232") (pin "15") (pinfunction "USBDP_15") (pintype "bidirectional"))
      (node (ref "USB") (pin "3") (pinfunction "3_3") (pintype "passive"))
      (node (ref "USB1") (pin "3") (pinfunction "3_3") (pintype "passive"))
    )
    (net (code "23") (name "/D-") (class "Default")
      (node (ref "FT232") (pin "16") (pinfunction "USBDM_16") (pintype "bidirectional"))
      (node (ref "USB") (pin "2") (pinfunction "2_2") (pintype "passive"))
      (node (ref "USB1") (pin "2") (pinfunction "2_2") (pintype "passive"))
    )
    (net (code "24") (name "/D0.0") (class "Default")
      (node (ref "SJ1") (pin "2") (pinfunction "2_2") (pintype "passive"))
      (node (ref "X_AXIS") (pin "DECAY0") (pinfunction "DECAY0_DECAY0") (pintype "bidirectional"))
    )
    (net (code "25") (name "/D0.1") (class "Default")
      (node (ref "SJ8") (pin "2") (pinfunction "2_2") (pintype "passive"))
      (node (ref "Y-AXIS") (pin "DECAY0") (pinfunction "DECAY0_DECAY0") (pintype "bidirectional"))
    )
    (net (code "26") (name "/D0.2") (class "Default")
      (node (ref "SJ9") (pin "2") (pinfunction "2_2") (pintype "passive"))
      (node (ref "Z_AXIS") (pin "DECAY0") (pinfunction "DECAY0_DECAY0") (pintype "bidirectional"))
    )
    (net (code "27") (name "/D0.3") (class "Default")
      (node (ref "EXT_1") (pin "DECAY0") (pinfunction "DECAY0_DECAY0") (pintype "bidirectional"))
      (node (ref "SJ13") (pin "2") (pinfunction "2_2") (pintype "passive"))
    )
    (net (code "28") (name "/D0.4") (class "Default")
      (node (ref "EXT_2") (pin "DECAY0") (pinfunction "DECAY0_DECAY0") (pintype "bidirectional"))
      (node (ref "SJ18") (pin "2") (pinfunction "2_2") (pintype "passive"))
    )
    (net (code "29") (name "/D1.0") (class "Default")
      (node (ref "SJ2") (pin "2") (pinfunction "2_2") (pintype "passive"))
      (node (ref "X_AXIS") (pin "DECAY1") (pinfunction "DECAY1_DECAY1") (pintype "bidirectional"))
    )
    (net (code "30") (name "/D1.1") (class "Default")
      (node (ref "SJ5") (pin "2") (pinfunction "2_2") (pintype "passive"))
      (node (ref "Y-AXIS") (pin "DECAY1") (pinfunction "DECAY1_DECAY1") (pintype "bidirectional"))
    )
    (net (code "31") (name "/D1.2") (class "Default")
      (node (ref "SJ10") (pin "2") (pinfunction "2_2") (pintype "passive"))
      (node (ref "Z_AXIS") (pin "DECAY1") (pinfunction "DECAY1_DECAY1") (pintype "bidirectional"))
    )
    (net (code "32") (name "/D1.3") (class "Default")
      (node (ref "EXT_1") (pin "DECAY1") (pinfunction "DECAY1_DECAY1") (pintype "bidirectional"))
      (node (ref "SJ14") (pin "2") (pinfunction "2_2") (pintype "passive"))
    )
    (net (code "33") (name "/D1.4") (class "Default")
      (node (ref "EXT_2") (pin "DECAY1") (pinfunction "DECAY1_DECAY1") (pintype "bidirectional"))
      (node (ref "SJ17") (pin "2") (pinfunction "2_2") (pintype "passive"))
    )
    (net (code "34") (name "/E-DIR") (class "Default")
      (node (ref "EXT_1") (pin "DIR") (pinfunction "DIR_DIR") (pintype "bidirectional"))
      (node (ref "IC1") (pin "24") (pinfunction "(PCINT21/TDI)PC5_24") (pintype "output"))
    )
    (net (code "35") (name "/E-STEP") (class "Default")
      (node (ref "EXT_1") (pin "STEP") (pinfunction "STEP_STEP") (pintype "bidirectional"))
      (node (ref "IC1") (pin "23") (pinfunction "(PCINT20/TDO)PC4_23") (pintype "output"))
    )
    (net (code "36") (name "/E-THERM") (class "Default")
      (node (ref "DBR1") (pin "2") (pinfunction "2_2") (pintype "passive"))
      (node (ref "IC1") (pin "34") (pinfunction "(PCINT3/ADC3)PA3_34") (pintype "bidirectional"))
    )
    (net (code "37") (name "/E2-DIR") (class "Default")
      (node (ref "IC1") (pin "21") (pinfunction "(PCINT18/TCK)PC2_21") (pintype "output"))
      (node (ref "X7") (pin "2") (pinfunction "S_2") (pintype "passive"))
    )
    (net (code "38") (name "/E2-DIR-C") (class "Default")
      (node (ref "EXT_2") (pin "DIR") (pinfunction "DIR_DIR") (pintype "bidirectional"))
      (node (ref "X29") (pin "1") (pinfunction "S_1") (pintype "passive"))
    )
    (net (code "39") (name "/E2-STEP") (class "Default")
      (node (ref "IC1") (pin "22") (pinfunction "(PCINT19/TMS)PC3_22") (pintype "output"))
      (node (ref "X5") (pin "2") (pinfunction "S_2") (pintype "passive"))
    )
    (net (code "40") (name "/E2-STEP-C") (class "Default")
      (node (ref "EXT_2") (pin "STEP") (pinfunction "STEP_STEP") (pintype "bidirectional"))
      (node (ref "X6") (pin "1") (pinfunction "S_1") (pintype "passive"))
    )
    (net (code "41") (name "/E2-THERM") (class "Default")
      (node (ref "DBR0") (pin "2") (pinfunction "2_2") (pintype "passive"))
      (node (ref "IC1") (pin "33") (pinfunction "(PCINT4/ADC4)PA4_33") (pintype "bidirectional"))
    )
    (net (code "42") (name "/E2_EN_C") (class "Default")
      (node (ref "EXT_2") (pin "ENABLE") (pinfunction "ENABLE_ENABLE") (pintype "bidirectional"))
      (node (ref "X4") (pin "1") (pinfunction "S_1") (pintype "passive"))
    )
    (net (code "43") (name "/ENC1") (class "Default")
      (node (ref "IC1") (pin "11") (pinfunction "(PCINT26/INT0)PD2_11") (pintype "bidirectional"))
      (node (ref "LCD_ENC") (pin "1") (pinfunction "1_1") (pintype "passive"))
    )
    (net (code "44") (name "/ENC2") (class "Default")
      (node (ref "IC1") (pin "12") (pinfunction "(PCINT27/INT1)PD3_12") (pintype "bidirectional"))
      (node (ref "LCD_ENC") (pin "3") (pinfunction "3_3") (pintype "passive"))
    )
    (net (code "45") (name "/FAN") (class "Default")
      (node (ref "IC1") (pin "15") (pinfunction "(PCINT30/OC2B/ICP)PD6_15") (pintype "bidirectional"))
      (node (ref "MOS_FAN") (pin "1") (pinfunction "G_1") (pintype "passive"))
      (node (ref "MOS_FAN1") (pin "G") (pinfunction "G_G") (pintype "bidirectional"))
      (node (ref "RG_F") (pin "1") (pinfunction "1_1") (pintype "passive"))
    )
    (net (code "46") (name "/HOTBED") (class "Default")
      (node (ref "HOTBED") (pin "1") (pinfunction "G_1") (pintype "passive"))
      (node (ref "HOTBED1") (pin "G") (pinfunction "G_G") (pintype "bidirectional"))
      (node (ref "IC1") (pin "14") (pinfunction "(PCINT29/OC1A)PD5_14") (pintype "bidirectional"))
      (node (ref "RG_B") (pin "1") (pinfunction "1_1") (pintype "passive"))
    )
    (net (code "47") (name "/HOTEND") (class "Default")
      (node (ref "HOTEND") (pin "1") (pinfunction "G_1") (pintype "passive"))
      (node (ref "HOTEND1") (pin "G") (pinfunction "G_G") (pintype "bidirectional"))
      (node (ref "IC1") (pin "13") (pinfunction "(PCINT28/OC1B)PD4_13") (pintype "bidirectional"))
      (node (ref "RG_E") (pin "1") (pinfunction "1_1") (pintype "passive"))
    )
    (net (code "48") (name "/M0.0") (class "Default")
      (node (ref "X31") (pin "1") (pinfunction "S_1") (pintype "passive"))
      (node (ref "X_AXIS") (pin "M0") (pinfunction "M0_M0") (pintype "bidirectional"))
    )
    (net (code "49") (name "/M0.1") (class "Default")
      (node (ref "X33") (pin "1") (pinfunction "S_1") (pintype "passive"))
      (node (ref "Y-AXIS") (pin "M0") (pinfunction "M0_M0") (pintype "bidirectional"))
    )
    (net (code "50") (name "/M0.2") (class "Default")
      (node (ref "X35") (pin "1") (pinfunction "S_1") (pintype "passive"))
      (node (ref "Z_AXIS") (pin "M0") (pinfunction "M0_M0") (pintype "bidirectional"))
    )
    (net (code "51") (name "/M0.3") (class "Default")
      (node (ref "EXT_1") (pin "M0") (pinfunction "M0_M0") (pintype "bidirectional"))
      (node (ref "X37") (pin "1") (pinfunction "S_1") (pintype "passive"))
    )
    (net (code "52") (name "/M0.4") (class "Default")
      (node (ref "EXT_2") (pin "M0") (pinfunction "M0_M0") (pintype "bidirectional"))
      (node (ref "X39") (pin "1") (pinfunction "S_1") (pintype "passive"))
    )
    (net (code "53") (name "/M1.0") (class "Default")
      (node (ref "X31") (pin "2") (pinfunction "S_2") (pintype "passive"))
      (node (ref "X_AXIS") (pin "M1") (pinfunction "M1_M1") (pintype "bidirectional"))
    )
    (net (code "54") (name "/M1.1") (class "Default")
      (node (ref "X33") (pin "2") (pinfunction "S_2") (pintype "passive"))
      (node (ref "Y-AXIS") (pin "M1") (pinfunction "M1_M1") (pintype "bidirectional"))
    )
    (net (code "55") (name "/M1.2") (class "Default")
      (node (ref "X35") (pin "2") (pinfunction "S_2") (pintype "passive"))
      (node (ref "Z_AXIS") (pin "M1") (pinfunction "M1_M1") (pintype "bidirectional"))
    )
    (net (code "56") (name "/M1.3") (class "Default")
      (node (ref "EXT_1") (pin "M1") (pinfunction "M1_M1") (pintype "bidirectional"))
      (node (ref "X37") (pin "2") (pinfunction "S_2") (pintype "passive"))
    )
    (net (code "57") (name "/M1.4") (class "Default")
      (node (ref "EXT_2") (pin "M1") (pinfunction "M1_M1") (pintype "bidirectional"))
      (node (ref "X39") (pin "2") (pinfunction "S_2") (pintype "passive"))
    )
    (net (code "58") (name "/MISO") (class "Default")
      (node (ref "IC1") (pin "2") (pinfunction "(PCINT14/MISO)PB6_2") (pintype "bidirectional"))
      (node (ref "ISP") (pin "6") (pinfunction "6_6") (pintype "passive"))
      (node (ref "SD") (pin "DAT0") (pinfunction "MISO_DAT0") (pintype "bidirectional"))
      (node (ref "USD") (pin "7") (pinfunction "DAT0_D0_7") (pintype "bidirectional"))
    )
    (net (code "59") (name "/MOS-1") (class "Default")
      (node (ref "MOS11") (pin "G") (pinfunction "G_G") (pintype "bidirectional"))
      (node (ref "MOS_1") (pin "1") (pinfunction "G_1") (pintype "passive"))
      (node (ref "RG_1") (pin "1") (pinfunction "1_1") (pintype "passive"))
      (node (ref "X5") (pin "1") (pinfunction "S_1") (pintype "passive"))
    )
    (net (code "60") (name "/MOS-2") (class "Default")
      (node (ref "MOS22") (pin "G") (pinfunction "G_G") (pintype "bidirectional"))
      (node (ref "MOS_2") (pin "1") (pinfunction "G_1") (pintype "passive"))
      (node (ref "RG_2") (pin "1") (pinfunction "1_1") (pintype "passive"))
      (node (ref "X3") (pin "1") (pinfunction "S_1") (pintype "passive"))
    )
    (net (code "61") (name "/MOSI") (class "Default")
      (node (ref "IC1") (pin "1") (pinfunction "(PCINT13/MOSI)PB5_1") (pintype "bidirectional"))
      (node (ref "ISP") (pin "3") (pinfunction "3_3") (pintype "passive"))
      (node (ref "LEVEL_SHIFTER") (pin "3") (pinfunction "I_3") (pintype "input"))
    )
    (net (code "62") (name "/MOSI_3V3") (class "Default")
      (node (ref "LEVEL_SHIFTER") (pin "2") (pinfunction "O_2") (pintype "output"))
      (node (ref "SD") (pin "CMD") (pinfunction "MOSI_CMD") (pintype "bidirectional"))
      (node (ref "USD") (pin "3") (pinfunction "CMD_DI_3") (pintype "bidirectional"))
    )
    (net (code "63") (name "/RESET") (class "Default")
      (node (ref "IC1") (pin "4") (pinfunction "RESET_4") (pintype "input"))
      (node (ref "ISP") (pin "2") (pinfunction "2_2") (pintype "passive"))
      (node (ref "PUP_RES") (pin "1") (pinfunction "1_1") (pintype "passive"))
      (node (ref "RESET") (pin "1") (pinfunction "S_1") (pintype "passive"))
      (node (ref "RESET") (pin "2") (pinfunction "S1_2") (pintype "passive"))
    )
    (net (code "64") (name "/RX") (class "Default")
      (node (ref "FT232") (pin "1") (pinfunction "TXD_1") (pintype "output"))
      (node (ref "IC1") (pin "9") (pinfunction "(PCINT24/RXD0)PD0_9") (pintype "bidirectional"))
    )
    (net (code "65") (name "/SCK") (class "Default")
      (node (ref "IC1") (pin "3") (pinfunction "(PCINT15/SCK)PB7_3") (pintype "bidirectional"))
      (node (ref "ISP") (pin "4") (pinfunction "4_4") (pintype "passive"))
      (node (ref "LEVEL_SHIFTER") (pin "7") (pinfunction "I_7") (pintype "input"))
    )
    (net (code "66") (name "/SCK_3V3") (class "Default")
      (node (ref "LEVEL_SHIFTER") (pin "6") (pinfunction "O_6") (pintype "output"))
      (node (ref "SD") (pin "CLK") (pinfunction "SCK_CLK") (pintype "bidirectional"))
      (node (ref "USD") (pin "5") (pinfunction "CLK_5") (pintype "bidirectional"))
    )
    (net (code "67") (name "/SCL") (class "Default")
      (node (ref "IC1") (pin "19") (pinfunction "(PCINT16/SCL)PC0_19") (pintype "output"))
      (node (ref "LCD_ENC") (pin "2") (pinfunction "2_2") (pintype "passive"))
    )
    (net (code "68") (name "/SD-CS") (class "Default")
      (node (ref "IC1") (pin "37") (pinfunction "(PCINT0/ADC0)PA0_37") (pintype "bidirectional"))
      (node (ref "LEVEL_SHIFTER") (pin "5") (pinfunction "I_5") (pintype "input"))
    )
    (net (code "69") (name "/SDA") (class "Default")
      (node (ref "IC1") (pin "20") (pinfunction "(PCINT17/SDA)PC1_20") (pintype "output"))
      (node (ref "LCD_ENC") (pin "4") (pinfunction "4_4") (pintype "passive"))
    )
    (net (code "70") (name "/STOPX") (class "Default")
      (node (ref "DBC3") (pin "1") (pinfunction "1_1") (pintype "passive"))
      (node (ref "DBR3") (pin "1") (pinfunction "1_1") (pintype "passive"))
      (node (ref "ENDSTOP") (pin "2") (pinfunction "2_2") (pintype "passive"))
      (node (ref "IC1") (pin "30") (pinfunction "(PCINT7/ADC7)PA7_30") (pintype "bidirectional"))
    )
    (net (code "71") (name "/STOPY") (class "Default")
      (node (ref "DBC4") (pin "1") (pinfunction "1_1") (pintype "passive"))
      (node (ref "DBR4") (pin "1") (pinfunction "1_1") (pintype "passive"))
      (node (ref "ENDSTOP") (pin "4") (pinfunction "4_4") (pintype "passive"))
      (node (ref "IC1") (pin "31") (pinfunction "(PCINT6/ADC6)PA6_31") (pintype "bidirectional"))
    )
    (net (code "72") (name "/STOPZ") (class "Default")
      (node (ref "DBC5") (pin "1") (pinfunction "1_1") (pintype "passive"))
      (node (ref "DBR5") (pin "1") (pinfunction "1_1") (pintype "passive"))
      (node (ref "ENDSTOP") (pin "6") (pinfunction "6_6") (pintype "passive"))
      (node (ref "IC1") (pin "32") (pinfunction "(PCINT5/ADC5)PA5_32") (pintype "bidirectional"))
    )
    (net (code "73") (name "/T0.0") (class "Default")
      (node (ref "X32") (pin "1") (pinfunction "S_1") (pintype "passive"))
      (node (ref "X_AXIS") (pin "TRQ0") (pinfunction "TRQ0_TRQ0") (pintype "bidirectional"))
    )
    (net (code "74") (name "/T0.1") (class "Default")
      (node (ref "X34") (pin "1") (pinfunction "S_1") (pintype "passive"))
      (node (ref "Y-AXIS") (pin "TRQ0") (pinfunction "TRQ0_TRQ0") (pintype "bidirectional"))
    )
    (net (code "75") (name "/T0.2") (class "Default")
      (node (ref "X36") (pin "1") (pinfunction "S_1") (pintype "passive"))
      (node (ref "Z_AXIS") (pin "TRQ0") (pinfunction "TRQ0_TRQ0") (pintype "bidirectional"))
    )
    (net (code "76") (name "/T0.3") (class "Default")
      (node (ref "EXT_1") (pin "TRQ0") (pinfunction "TRQ0_TRQ0") (pintype "bidirectional"))
      (node (ref "X38") (pin "1") (pinfunction "S_1") (pintype "passive"))
    )
    (net (code "77") (name "/T0.4") (class "Default")
      (node (ref "EXT_2") (pin "TRQ0") (pinfunction "TRQ0_TRQ0") (pintype "bidirectional"))
      (node (ref "X40") (pin "1") (pinfunction "S_1") (pintype "passive"))
    )
    (net (code "78") (name "/T1.0") (class "Default")
      (node (ref "X32") (pin "2") (pinfunction "S_2") (pintype "passive"))
      (node (ref "X_AXIS") (pin "TRQ1") (pinfunction "TRQ1_TRQ1") (pintype "bidirectional"))
    )
    (net (code "79") (name "/T1.1") (class "Default")
      (node (ref "X34") (pin "2") (pinfunction "S_2") (pintype "passive"))
      (node (ref "Y-AXIS") (pin "TRQ1") (pinfunction "TRQ1_TRQ1") (pintype "bidirectional"))
    )
    (net (code "80") (name "/T1.2") (class "Default")
      (node (ref "X36") (pin "2") (pinfunction "S_2") (pintype "passive"))
      (node (ref "Z_AXIS") (pin "TRQ1") (pinfunction "TRQ1_TRQ1") (pintype "bidirectional"))
    )
    (net (code "81") (name "/T1.3") (class "Default")
      (node (ref "EXT_1") (pin "TRQ1") (pinfunction "TRQ1_TRQ1") (pintype "bidirectional"))
      (node (ref "X38") (pin "2") (pinfunction "S_2") (pintype "passive"))
    )
    (net (code "82") (name "/T1.4") (class "Default")
      (node (ref "EXT_2") (pin "TRQ1") (pinfunction "TRQ1_TRQ1") (pintype "bidirectional"))
      (node (ref "X40") (pin "2") (pinfunction "S_2") (pintype "passive"))
    )
    (net (code "83") (name "/TOFF.0") (class "Default")
      (node (ref "SJ3") (pin "2") (pinfunction "2_2") (pintype "passive"))
      (node (ref "X_AXIS") (pin "TOFF") (pinfunction "TOFF_TOFF") (pintype "bidirectional"))
    )
    (net (code "84") (name "/TOFF.1") (class "Default")
      (node (ref "SJ7") (pin "2") (pinfunction "2_2") (pintype "passive"))
      (node (ref "Y-AXIS") (pin "TOFF") (pinfunction "TOFF_TOFF") (pintype "bidirectional"))
    )
    (net (code "85") (name "/TOFF.2") (class "Default")
      (node (ref "SJ11") (pin "2") (pinfunction "2_2") (pintype "passive"))
      (node (ref "Z_AXIS") (pin "TOFF") (pinfunction "TOFF_TOFF") (pintype "bidirectional"))
    )
    (net (code "86") (name "/TOFF.3") (class "Default")
      (node (ref "EXT_1") (pin "TOFF") (pinfunction "TOFF_TOFF") (pintype "bidirectional"))
      (node (ref "SJ16") (pin "2") (pinfunction "2_2") (pintype "passive"))
    )
    (net (code "87") (name "/TOFF.4") (class "Default")
      (node (ref "EXT_2") (pin "TOFF") (pinfunction "TOFF_TOFF") (pintype "bidirectional"))
      (node (ref "SJ19") (pin "2") (pinfunction "2_2") (pintype "passive"))
    )
    (net (code "88") (name "/TX") (class "Default")
      (node (ref "FT232") (pin "5") (pinfunction "RXD_5") (pintype "input"))
      (node (ref "IC1") (pin "10") (pinfunction "(PCINT25/TXD0)PD1_10") (pintype "bidirectional"))
    )
    (net (code "89") (name "/VIN") (class "Default")
      (node (ref "7805") (pin "1") (pinfunction "VI_1") (pintype "input"))
      (node (ref "CDEC0.0") (pin "1") (pinfunction "1_1") (pintype "passive"))
      (node (ref "CDEC0.1") (pin "1") (pinfunction "1_1") (pintype "passive"))
      (node (ref "CDEC0.2") (pin "+") (pinfunction "+_+") (pintype "passive"))
      (node (ref "CDEC1.0") (pin "1") (pinfunction "1_1") (pintype "passive"))
      (node (ref "CDEC1.1") (pin "+") (pinfunction "+_+") (pintype "passive"))
      (node (ref "CDEC1.2") (pin "1") (pinfunction "1_1") (pintype "passive"))
      (node (ref "CDEC2.0") (pin "1") (pinfunction "1_1") (pintype "passive"))
      (node (ref "CDEC2.1") (pin "+") (pinfunction "+_+") (pintype "passive"))
      (node (ref "CDEC2.2") (pin "1") (pinfunction "1_1") (pintype "passive"))
      (node (ref "CDEC3.0") (pin "1") (pinfunction "1_1") (pintype "passive"))
      (node (ref "CDEC3.1") (pin "+") (pinfunction "+_+") (pintype "passive"))
      (node (ref "CDEC3.2") (pin "1") (pinfunction "1_1") (pintype "passive"))
      (node (ref "CDEC4.0") (pin "1") (pinfunction "1_1") (pintype "passive"))
      (node (ref "CDEC4.1") (pin "+") (pinfunction "+_+") (pintype "passive"))
      (node (ref "CDEC4.2") (pin "1") (pinfunction "1_1") (pintype "passive"))
      (node (ref "CPO0") (pin "2") (pinfunction "2_2") (pintype "passive"))
      (node (ref "CPO1") (pin "2") (pinfunction "2_2") (pintype "passive"))
      (node (ref "CPO2") (pin "2") (pinfunction "2_2") (pintype "passive"))
      (node (ref "CPO3") (pin "2") (pinfunction "2_2") (pintype "passive"))
      (node (ref "CPO4") (pin "2") (pinfunction "2_2") (pintype "passive"))
      (node (ref "C_HOTB") (pin "2") (pinfunction "KL_2") (pintype "passive"))
      (node (ref "EXT_1") (pin "VM") (pinfunction "VM_VM") (pintype "bidirectional"))
      (node (ref "EXT_1") (pin "VM1") (pinfunction "VM1_VM1") (pintype "bidirectional"))
      (node (ref "EXT_2") (pin "VM") (pinfunction "VM_VM") (pintype "bidirectional"))
      (node (ref "EXT_2") (pin "VM1") (pinfunction "VM1_VM1") (pintype "bidirectional"))
      (node (ref "FANC") (pin "2") (pinfunction "KL_2") (pintype "passive"))
      (node (ref "HOTE") (pin "2") (pinfunction "KL_2") (pintype "passive"))
      (node (ref "HOTE2") (pin "2") (pinfunction "KL_2") (pintype "passive"))
      (node (ref "LDOCIN") (pin "1") (pinfunction "1_1") (pintype "passive"))
      (node (ref "MOS") (pin "2") (pinfunction "KL_2") (pintype "passive"))
      (node (ref "REN1") (pin "2") (pinfunction "2_2") (pintype "passive"))
      (node (ref "SUPPLY") (pin "2") (pinfunction "VIN_2") (pintype "bidirectional"))
      (node (ref "SWT_CIN") (pin "2") (pinfunction "2_2") (pintype "passive"))
      (node (ref "VIN") (pin "1") (pinfunction "KL_1") (pintype "passive"))
      (node (ref "VIN") (pin "2") (pinfunction "KL_2") (pintype "passive"))
      (node (ref "X_AXIS") (pin "VM") (pinfunction "VM_VM") (pintype "bidirectional"))
      (node (ref "X_AXIS") (pin "VM1") (pinfunction "VM1_VM1") (pintype "bidirectional"))
      (node (ref "Y-AXIS") (pin "VM") (pinfunction "VM_VM") (pintype "bidirectional"))
      (node (ref "Y-AXIS") (pin "VM1") (pinfunction "VM1_VM1") (pintype "bidirectional"))
      (node (ref "Z_AXIS") (pin "VM") (pinfunction "VM_VM") (pintype "bidirectional"))
      (node (ref "Z_AXIS") (pin "VM1") (pinfunction "VM1_VM1") (pintype "bidirectional"))
    )
    (net (code "90") (name "/X-DIR") (class "Default")
      (node (ref "IC1") (pin "44") (pinfunction "(PCINT12/OC0B/~{SS})PB4_44") (pintype "bidirectional"))
      (node (ref "X_AXIS") (pin "DIR") (pinfunction "DIR_DIR") (pintype "bidirectional"))
    )
    (net (code "91") (name "/X-STEP") (class "Default")
      (node (ref "IC1") (pin "43") (pinfunction "(PCINT11/OC0A/AIN1)PB3_43") (pintype "bidirectional"))
      (node (ref "X_AXIS") (pin "STEP") (pinfunction "STEP_STEP") (pintype "bidirectional"))
    )
    (net (code "92") (name "/XYE_EN") (class "Default")
      (node (ref "EXT_1") (pin "ENABLE") (pinfunction "ENABLE_ENABLE") (pintype "bidirectional"))
      (node (ref "IC1") (pin "40") (pinfunction "(PCINT8/XCK0/T0)PB0_40") (pintype "bidirectional"))
      (node (ref "X3") (pin "2") (pinfunction "S_2") (pintype "passive"))
      (node (ref "X_AXIS") (pin "ENABLE") (pinfunction "ENABLE_ENABLE") (pintype "bidirectional"))
      (node (ref "Y-AXIS") (pin "ENABLE") (pinfunction "ENABLE_ENABLE") (pintype "bidirectional"))
    )
    (net (code "93") (name "/Y-DIR") (class "Default")
      (node (ref "IC1") (pin "42") (pinfunction "(PCINT10/INT2/AIN0)PB2_42") (pintype "bidirectional"))
      (node (ref "Y-AXIS") (pin "DIR") (pinfunction "DIR_DIR") (pintype "bidirectional"))
    )
    (net (code "94") (name "/Y-STEP") (class "Default")
      (node (ref "IC1") (pin "41") (pinfunction "(PCINT9/CLKO/T1)PB1_41") (pintype "bidirectional"))
      (node (ref "Y-AXIS") (pin "STEP") (pinfunction "STEP_STEP") (pintype "bidirectional"))
    )
    (net (code "95") (name "/Z-DIR") (class "Default")
      (node (ref "IC1") (pin "26") (pinfunction "(PCINT23/TOSC2)PC7_26") (pintype "output"))
      (node (ref "X29") (pin "2") (pinfunction "S_2") (pintype "passive"))
      (node (ref "Z_AXIS") (pin "DIR") (pinfunction "DIR_DIR") (pintype "bidirectional"))
    )
    (net (code "96") (name "/Z-EN") (class "Default")
      (node (ref "IC1") (pin "16") (pinfunction "(PCINT31/OC2A)PD7_16") (pintype "bidirectional"))
      (node (ref "X4") (pin "2") (pinfunction "S_2") (pintype "passive"))
      (node (ref "Z_AXIS") (pin "ENABLE") (pinfunction "ENABLE_ENABLE") (pintype "bidirectional"))
    )
    (net (code "97") (name "/Z-STEP") (class "Default")
      (node (ref "IC1") (pin "25") (pinfunction "(PCINT22/TOSC1)PC6_25") (pintype "output"))
      (node (ref "X6") (pin "2") (pinfunction "S_2") (pintype "passive"))
      (node (ref "Z_AXIS") (pin "STEP") (pinfunction "STEP_STEP") (pintype "bidirectional"))
    )
    (net (code "98") (name "GND") (class "Default")
      (node (ref "3V3_CDEC") (pin "2") (pinfunction "2_2") (pintype "passive"))
      (node (ref "7805") (pin "2") (pinfunction "GND_2") (pintype "passive"))
      (node (ref "AISEN0") (pin "2") (pinfunction "2_2") (pintype "passive"))
      (node (ref "AISEN1") (pin "2") (pinfunction "2_2") (pintype "passive"))
      (node (ref "AISEN2") (pin "2") (pinfunction "2_2") (pintype "passive"))
      (node (ref "AISEN3") (pin "2") (pinfunction "2_2") (pintype "passive"))
      (node (ref "AISEN4") (pin "2") (pinfunction "2_2") (pintype "passive"))
      (node (ref "ATCDEC1") (pin "1") (pinfunction "1_1") (pintype "passive"))
      (node (ref "ATCDEC3") (pin "1") (pinfunction "1_1") (pintype "passive"))
      (node (ref "BISEN0") (pin "2") (pinfunction "2_2") (pintype "passive"))
      (node (ref "BISEN1") (pin "2") (pinfunction "2_2") (pintype "passive"))
      (node (ref "BISEN2") (pin "2") (pinfunction "2_2") (pintype "passive"))
      (node (ref "BISEN3") (pin "2") (pinfunction "2_2") (pintype "passive"))
      (node (ref "BISEN4") (pin "2") (pinfunction "2_2") (pintype "passive"))
      (node (ref "B_THERM") (pin "2") (pinfunction "2_2") (pintype "passive"))
      (node (ref "CADC") (pin "2") (pinfunction "2_2") (pintype "passive"))
      (node (ref "CCOMP") (pin "1") (pinfunction "1_1") (pintype "passive"))
      (node (ref "CCOMP1") (pin "1") (pinfunction "1_1") (pintype "passive"))
      (node (ref "CDEC0.0") (pin "2") (pinfunction "2_2") (pintype "passive"))
      (node (ref "CDEC0.1") (pin "2") (pinfunction "2_2") (pintype "passive"))
      (node (ref "CDEC0.2") (pin "-") (pinfunction "-_-") (pintype "passive"))
      (node (ref "CDEC0.3") (pin "2") (pinfunction "2_2") (pintype "passive"))
      (node (ref "CDEC1.0") (pin "2") (pinfunction "2_2") (pintype "passive"))
      (node (ref "CDEC1.1") (pin "-") (pinfunction "-_-") (pintype "passive"))
      (node (ref "CDEC1.2") (pin "2") (pinfunction "2_2") (pintype "passive"))
      (node (ref "CDEC1.3") (pin "2") (pinfunction "2_2") (pintype "passive"))
      (node (ref "CDEC2.0") (pin "2") (pinfunction "2_2") (pintype "passive"))
      (node (ref "CDEC2.1") (pin "-") (pinfunction "-_-") (pintype "passive"))
      (node (ref "CDEC2.2") (pin "2") (pinfunction "2_2") (pintype "passive"))
      (node (ref "CDEC2.3") (pin "2") (pinfunction "2_2") (pintype "passive"))
      (node (ref "CDEC3.0") (pin "2") (pinfunction "2_2") (pintype "passive"))
      (node (ref "CDEC3.1") (pin "-") (pinfunction "-_-") (pintype "passive"))
      (node (ref "CDEC3.2") (pin "2") (pinfunction "2_2") (pintype "passive"))
      (node (ref "CDEC3.3") (pin "2") (pinfunction "2_2") (pintype "passive"))
      (node (ref "CDEC4.0") (pin "2") (pinfunction "2_2") (pintype "passive"))
      (node (ref "CDEC4.1") (pin "-") (pinfunction "-_-") (pintype "passive"))
      (node (ref "CDEC4.2") (pin "2") (pinfunction "2_2") (pintype "passive"))
      (node (ref "CDEC4.3") (pin "2") (pinfunction "2_2") (pintype "passive"))
      (node (ref "CDECREF1") (pin "1") (pinfunction "1_1") (pintype "passive"))
      (node (ref "CSS") (pin "1") (pinfunction "1_1") (pintype "passive"))
      (node (ref "C_Q1") (pin "2") (pinfunction "2_2") (pintype "passive"))
      (node (ref "C_Q2") (pin "1") (pinfunction "1_1") (pintype "passive"))
      (node (ref "D1") (pin "A") (pinfunction "A_A") (pintype "passive"))
      (node (ref "DBC0") (pin "2") (pinfunction "2_2") (pintype "passive"))
      (node (ref "DBC1") (pin "2") (pinfunction "2_2") (pintype "passive"))
      (node (ref "DBC2") (pin "2") (pinfunction "2_2") (pintype "passive"))
      (node (ref "DBC3") (pin "2") (pinfunction "2_2") (pintype "passive"))
      (node (ref "DBC4") (pin "2") (pinfunction "2_2") (pintype "passive"))
      (node (ref "DBC5") (pin "2") (pinfunction "2_2") (pintype "passive"))
      (node (ref "E1_THERM") (pin "2") (pinfunction "2_2") (pintype "passive"))
      (node (ref "E2_THERM") (pin "2") (pinfunction "2_2") (pintype "passive"))
      (node (ref "EXT_1") (pin "GND") (pinfunction "GND_GND") (pintype "bidirectional"))
      (node (ref "EXT_1") (pin "GND1") (pinfunction "GND1_GND1") (pintype "bidirectional"))
      (node (ref "EXT_1") (pin "GND2") (pinfunction "GND_GND2") (pintype "bidirectional"))
      (node (ref "EXT_2") (pin "GND") (pinfunction "GND_GND") (pintype "bidirectional"))
      (node (ref "EXT_2") (pin "GND1") (pinfunction "GND1_GND1") (pintype "bidirectional"))
      (node (ref "EXT_2") (pin "GND2") (pinfunction "GND_GND2") (pintype "bidirectional"))
      (node (ref "FT232") (pin "18") (pinfunction "GND_18") (pintype "power_in"))
      (node (ref "FT232") (pin "21") (pinfunction "GND_21") (pintype "power_in"))
      (node (ref "FT232") (pin "25") (pinfunction "GND_25") (pintype "power_in"))
      (node (ref "FT232") (pin "26") (pinfunction "TEST_26") (pintype "input"))
      (node (ref "FT232") (pin "7") (pinfunction "GND_7") (pintype "power_in"))
      (node (ref "FT_CDEC") (pin "1") (pinfunction "1_1") (pintype "passive"))
      (node (ref "GND") (pin "1") (pinfunction "KL_1") (pintype "passive"))
      (node (ref "GND") (pin "2") (pinfunction "KL_2") (pintype "passive"))
      (node (ref "HOTBED") (pin "2") (pinfunction "S_2") (pintype "passive"))
      (node (ref "HOTBED1") (pin "S") (pinfunction "S_S") (pintype "bidirectional"))
      (node (ref "HOTEND") (pin "2") (pinfunction "S_2") (pintype "passive"))
      (node (ref "HOTEND1") (pin "S") (pinfunction "S_S") (pintype "bidirectional"))
      (node (ref "IC1") (pin "18") (pinfunction "GND_18") (pintype "power_in"))
      (node (ref "IC1") (pin "28") (pinfunction "GND_28") (pintype "power_in"))
      (node (ref "IC1") (pin "39") (pinfunction "GND_39") (pintype "power_in"))
      (node (ref "IC1") (pin "6") (pinfunction "GND_6") (pintype "power_in"))
      (node (ref "ISP") (pin "1") (pinfunction "1_1") (pintype "passive"))
      (node (ref "LCD_ENC") (pin "7") (pinfunction "7_7") (pintype "passive"))
      (node (ref "LCD_ENC") (pin "8") (pinfunction "8_8") (pintype "passive"))
      (node (ref "LDOCIN") (pin "2") (pinfunction "2_2") (pintype "passive"))
      (node (ref "LDOCOUT") (pin "2") (pinfunction "2_2") (pintype "passive"))
      (node (ref "LEVEL_SHIFTER") (pin "8") (pinfunction "VSS_8") (pintype "power_in"))
      (node (ref "MOS11") (pin "S") (pinfunction "S_S") (pintype "bidirectional"))
      (node (ref "MOS22") (pin "S") (pinfunction "S_S") (pintype "bidirectional"))
      (node (ref "MOS_1") (pin "2") (pinfunction "S_2") (pintype "passive"))
      (node (ref "MOS_2") (pin "2") (pinfunction "S_2") (pintype "passive"))
      (node (ref "MOS_FAN") (pin "2") (pinfunction "S_2") (pintype "passive"))
      (node (ref "MOS_FAN1") (pin "S") (pinfunction "S_S") (pintype "bidirectional"))
      (node (ref "REN2") (pin "1") (pinfunction "1_1") (pintype "passive"))
      (node (ref "RESET") (pin "3") (pinfunction "P_3") (pintype "passive"))
      (node (ref "RESET") (pin "4") (pinfunction "P1_4") (pintype "passive"))
      (node (ref "RF2") (pin "1") (pinfunction "1_1") (pintype "passive"))
      (node (ref "RG_1") (pin "2") (pinfunction "2_2") (pintype "passive"))
      (node (ref "RG_2") (pin "2") (pinfunction "2_2") (pintype "passive"))
      (node (ref "RG_B") (pin "2") (pinfunction "2_2") (pintype "passive"))
      (node (ref "RG_E") (pin "2") (pinfunction "2_2") (pintype "passive"))
      (node (ref "RG_F") (pin "2") (pinfunction "2_2") (pintype "passive"))
      (node (ref "RRT") (pin "1") (pinfunction "1_1") (pintype "passive"))
      (node (ref "SD") (pin "VSS1") (pinfunction "GND_VSS1") (pintype "bidirectional"))
      (node (ref "SD") (pin "VSS2") (pinfunction "GND1_VSS2") (pintype "bidirectional"))
      (node (ref "SJ1") (pin "3") (pinfunction "3_3") (pintype "passive"))
      (node (ref "SJ10") (pin "3") (pinfunction "3_3") (pintype "passive"))
      (node (ref "SJ11") (pin "3") (pinfunction "3_3") (pintype "passive"))
      (node (ref "SJ12") (pin "3") (pinfunction "3_3") (pintype "passive"))
      (node (ref "SJ13") (pin "3") (pinfunction "3_3") (pintype "passive"))
      (node (ref "SJ14") (pin "3") (pinfunction "3_3") (pintype "passive"))
      (node (ref "SJ15") (pin "3") (pinfunction "3_3") (pintype "passive"))
      (node (ref "SJ16") (pin "3") (pinfunction "3_3") (pintype "passive"))
      (node (ref "SJ17") (pin "3") (pinfunction "3_3") (pintype "passive"))
      (node (ref "SJ18") (pin "3") (pinfunction "3_3") (pintype "passive"))
      (node (ref "SJ19") (pin "3") (pinfunction "3_3") (pintype "passive"))
      (node (ref "SJ2") (pin "3") (pinfunction "3_3") (pintype "passive"))
      (node (ref "SJ20") (pin "3") (pinfunction "3_3") (pintype "passive"))
      (node (ref "SJ3") (pin "3") (pinfunction "3_3") (pintype "passive"))
      (node (ref "SJ4") (pin "3") (pinfunction "3_3") (pintype "passive"))
      (node (ref "SJ5") (pin "3") (pinfunction "3_3") (pintype "passive"))
      (node (ref "SJ6") (pin "3") (pinfunction "3_3") (pintype "passive"))
      (node (ref "SJ7") (pin "3") (pinfunction "3_3") (pintype "passive"))
      (node (ref "SJ8") (pin "3") (pinfunction "3_3") (pintype "passive"))
      (node (ref "SJ9") (pin "3") (pinfunction "3_3") (pintype "passive"))
      (node (ref "SUPPLY") (pin "9") (pinfunction "GND_9") (pintype "bidirectional"))
      (node (ref "SUPPLY") (pin "GND") (pinfunction "GND_GND") (pintype "bidirectional"))
      (node (ref "SWT_CIN") (pin "1") (pinfunction "1_1") (pintype "passive"))
      (node (ref "SWT_COUT") (pin "1") (pinfunction "1_1") (pintype "passive"))
      (node (ref "T0") (pin "1") (pinfunction "1_1") (pintype "bidirectional"))
      (node (ref "T1") (pin "1") (pinfunction "1_1") (pintype "bidirectional"))
      (node (ref "T2") (pin "1") (pinfunction "1_1") (pintype "bidirectional"))
      (node (ref "T3") (pin "1") (pinfunction "1_1") (pintype "bidirectional"))
      (node (ref "T4") (pin "1") (pinfunction "1_1") (pintype "bidirectional"))
      (node (ref "USB") (pin "4") (pinfunction "4_4") (pintype "passive"))
      (node (ref "USB1") (pin "4") (pinfunction "4_4") (pintype "passive"))
      (node (ref "USD") (pin "6") (pinfunction "VSS_6") (pintype "bidirectional"))
      (node (ref "X1") (pin "GND1") (pinfunction "GND_GND1") (pintype "bidirectional"))
      (node (ref "X1") (pin "GND2") (pinfunction "GND_GND2") (pintype "bidirectional"))
      (node (ref "X14") (pin "1") (pinfunction "S_1") (pintype "passive"))
      (node (ref "X14") (pin "2") (pinfunction "S_2") (pintype "passive"))
      (node (ref "X15") (pin "1") (pinfunction "S_1") (pintype "passive"))
      (node (ref "X15") (pin "2") (pinfunction "S_2") (pintype "passive"))
      (node (ref "X16") (pin "1") (pinfunction "S_1") (pintype "passive"))
      (node (ref "X16") (pin "2") (pinfunction "S_2") (pintype "passive"))
      (node (ref "X21") (pin "1") (pinfunction "S_1") (pintype "passive"))
      (node (ref "X21") (pin "2") (pinfunction "S_2") (pintype "passive"))
      (node (ref "X22") (pin "1") (pinfunction "S_1") (pintype "passive"))
      (node (ref "X22") (pin "2") (pinfunction "S_2") (pintype "passive"))
      (node (ref "X25") (pin "1") (pinfunction "S_1") (pintype "passive"))
      (node (ref "X25") (pin "2") (pinfunction "S_2") (pintype "passive"))
      (node (ref "X26") (pin "1") (pinfunction "S_1") (pintype "passive"))
      (node (ref "X26") (pin "2") (pinfunction "S_2") (pintype "passive"))
      (node (ref "X27") (pin "1") (pinfunction "S_1") (pintype "passive"))
      (node (ref "X27") (pin "2") (pinfunction "S_2") (pintype "passive"))
      (node (ref "X28") (pin "1") (pinfunction "S_1") (pintype "passive"))
      (node (ref "X28") (pin "2") (pinfunction "S_2") (pintype "passive"))
      (node (ref "X9") (pin "1") (pinfunction "S_1") (pintype "passive"))
      (node (ref "X9") (pin "2") (pinfunction "S_2") (pintype "passive"))
      (node (ref "X_AXIS") (pin "GND") (pinfunction "GND_GND") (pintype "bidirectional"))
      (node (ref "X_AXIS") (pin "GND1") (pinfunction "GND1_GND1") (pintype "bidirectional"))
      (node (ref "X_AXIS") (pin "GND2") (pinfunction "GND_GND2") (pintype "bidirectional"))
      (node (ref "Y-AXIS") (pin "GND") (pinfunction "GND_GND") (pintype "bidirectional"))
      (node (ref "Y-AXIS") (pin "GND1") (pinfunction "GND1_GND1") (pintype "bidirectional"))
      (node (ref "Y-AXIS") (pin "GND2") (pinfunction "GND_GND2") (pintype "bidirectional"))
      (node (ref "Z_AXIS") (pin "GND") (pinfunction "GND_GND") (pintype "bidirectional"))
      (node (ref "Z_AXIS") (pin "GND1") (pinfunction "GND1_GND1") (pintype "bidirectional"))
      (node (ref "Z_AXIS") (pin "GND2") (pinfunction "GND_GND2") (pintype "bidirectional"))
    )
    (net (code "99") (name "Net-(AISEN0-Pad1)") (class "Default")
      (node (ref "AISEN0") (pin "1") (pinfunction "1_1") (pintype "passive"))
      (node (ref "X_AXIS") (pin "AISEN") (pinfunction "AISEN_AISEN") (pintype "bidirectional"))
    )
    (net (code "100") (name "Net-(AISEN1-Pad1)") (class "Default")
      (node (ref "AISEN1") (pin "1") (pinfunction "1_1") (pintype "passive"))
      (node (ref "Y-AXIS") (pin "AISEN") (pinfunction "AISEN_AISEN") (pintype "bidirectional"))
    )
    (net (code "101") (name "Net-(AISEN2-Pad1)") (class "Default")
      (node (ref "AISEN2") (pin "1") (pinfunction "1_1") (pintype "passive"))
      (node (ref "Z_AXIS") (pin "AISEN") (pinfunction "AISEN_AISEN") (pintype "bidirectional"))
    )
    (net (code "102") (name "Net-(AISEN3-Pad1)") (class "Default")
      (node (ref "AISEN3") (pin "1") (pinfunction "1_1") (pintype "passive"))
      (node (ref "EXT_1") (pin "AISEN") (pinfunction "AISEN_AISEN") (pintype "bidirectional"))
    )
    (net (code "103") (name "Net-(AISEN4-Pad1)") (class "Default")
      (node (ref "AISEN4") (pin "1") (pinfunction "1_1") (pintype "passive"))
      (node (ref "EXT_2") (pin "AISEN") (pinfunction "AISEN_AISEN") (pintype "bidirectional"))
    )
    (net (code "104") (name "Net-(BISEN0-Pad1)") (class "Default")
      (node (ref "BISEN0") (pin "1") (pinfunction "1_1") (pintype "passive"))
      (node (ref "X_AXIS") (pin "BISEN") (pinfunction "BISEN_BISEN") (pintype "bidirectional"))
    )
    (net (code "105") (name "Net-(BISEN1-Pad1)") (class "Default")
      (node (ref "BISEN1") (pin "1") (pinfunction "1_1") (pintype "passive"))
      (node (ref "Y-AXIS") (pin "BISEN") (pinfunction "BISEN_BISEN") (pintype "bidirectional"))
    )
    (net (code "106") (name "Net-(BISEN2-Pad1)") (class "Default")
      (node (ref "BISEN2") (pin "1") (pinfunction "1_1") (pintype "passive"))
      (node (ref "Z_AXIS") (pin "BISEN") (pinfunction "BISEN_BISEN") (pintype "bidirectional"))
    )
    (net (code "107") (name "Net-(BISEN3-Pad1)") (class "Default")
      (node (ref "BISEN3") (pin "1") (pinfunction "1_1") (pintype "passive"))
      (node (ref "EXT_1") (pin "BISEN") (pinfunction "BISEN_BISEN") (pintype "bidirectional"))
    )
    (net (code "108") (name "Net-(BISEN4-Pad1)") (class "Default")
      (node (ref "BISEN4") (pin "1") (pinfunction "1_1") (pintype "passive"))
      (node (ref "EXT_2") (pin "BISEN") (pinfunction "BISEN_BISEN") (pintype "bidirectional"))
    )
    (net (code "109") (name "Net-(B_THERM-Pad1)") (class "Default")
      (node (ref "B_THERM") (pin "1") (pinfunction "1_1") (pintype "passive"))
      (node (ref "DBC2") (pin "1") (pinfunction "1_1") (pintype "passive"))
      (node (ref "DBR2") (pin "1") (pinfunction "1_1") (pintype "passive"))
    )
    (net (code "110") (name "Net-(CCOMP1-Pad2)") (class "Default")
      (node (ref "CCOMP1") (pin "2") (pinfunction "2_2") (pintype "passive"))
      (node (ref "RCOMP") (pin "1") (pinfunction "1_1") (pintype "passive"))
    )
    (net (code "111") (name "Net-(CDEC0.3-Pad1)") (class "Default")
      (node (ref "CDEC0.3") (pin "1") (pinfunction "1_1") (pintype "passive"))
      (node (ref "RVREF0") (pin "1") (pinfunction "1_1") (pintype "passive"))
      (node (ref "X_AXIS") (pin "V3P3") (pinfunction "V3P3_V3P3") (pintype "bidirectional"))
    )
    (net (code "112") (name "Net-(CDEC1.3-Pad1)") (class "Default")
      (node (ref "CDEC1.3") (pin "1") (pinfunction "1_1") (pintype "passive"))
      (node (ref "RVREF1") (pin "1") (pinfunction "1_1") (pintype "passive"))
      (node (ref "Y-AXIS") (pin "V3P3") (pinfunction "V3P3_V3P3") (pintype "bidirectional"))
    )
    (net (code "113") (name "Net-(CDEC2.3-Pad1)") (class "Default")
      (node (ref "CDEC2.3") (pin "1") (pinfunction "1_1") (pintype "passive"))
      (node (ref "RVREF2") (pin "1") (pinfunction "1_1") (pintype "passive"))
      (node (ref "Z_AXIS") (pin "V3P3") (pinfunction "V3P3_V3P3") (pintype "bidirectional"))
    )
    (net (code "114") (name "Net-(CDEC3.3-Pad1)") (class "Default")
      (node (ref "CDEC3.3") (pin "1") (pinfunction "1_1") (pintype "passive"))
      (node (ref "EXT_1") (pin "V3P3") (pinfunction "V3P3_V3P3") (pintype "bidirectional"))
      (node (ref "RVREF3") (pin "1") (pinfunction "1_1") (pintype "passive"))
    )
    (net (code "115") (name "Net-(CDEC4.3-Pad1)") (class "Default")
      (node (ref "CDEC4.3") (pin "1") (pinfunction "1_1") (pintype "passive"))
      (node (ref "EXT_2") (pin "V3P3") (pinfunction "V3P3_V3P3") (pintype "bidirectional"))
      (node (ref "RVREF4") (pin "1") (pinfunction "1_1") (pintype "passive"))
    )
    (net (code "116") (name "Net-(CP0-Pad1)") (class "Default")
      (node (ref "CP0") (pin "1") (pinfunction "1_1") (pintype "passive"))
      (node (ref "X_AXIS") (pin "CPL") (pinfunction "CPL_CPL") (pintype "bidirectional"))
    )
    (net (code "117") (name "Net-(CP0-Pad2)") (class "Default")
      (node (ref "CP0") (pin "2") (pinfunction "2_2") (pintype "passive"))
      (node (ref "X_AXIS") (pin "CPH") (pinfunction "CPH_CPH") (pintype "bidirectional"))
    )
    (net (code "118") (name "Net-(CP1-Pad1)") (class "Default")
      (node (ref "CP1") (pin "1") (pinfunction "1_1") (pintype "passive"))
      (node (ref "Y-AXIS") (pin "CPL") (pinfunction "CPL_CPL") (pintype "bidirectional"))
    )
    (net (code "119") (name "Net-(CP1-Pad2)") (class "Default")
      (node (ref "CP1") (pin "2") (pinfunction "2_2") (pintype "passive"))
      (node (ref "Y-AXIS") (pin "CPH") (pinfunction "CPH_CPH") (pintype "bidirectional"))
    )
    (net (code "120") (name "Net-(CP2-Pad1)") (class "Default")
      (node (ref "CP2") (pin "1") (pinfunction "1_1") (pintype "passive"))
      (node (ref "Z_AXIS") (pin "CPL") (pinfunction "CPL_CPL") (pintype "bidirectional"))
    )
    (net (code "121") (name "Net-(CP2-Pad2)") (class "Default")
      (node (ref "CP2") (pin "2") (pinfunction "2_2") (pintype "passive"))
      (node (ref "Z_AXIS") (pin "CPH") (pinfunction "CPH_CPH") (pintype "bidirectional"))
    )
    (net (code "122") (name "Net-(CP3-Pad1)") (class "Default")
      (node (ref "CP3") (pin "1") (pinfunction "1_1") (pintype "passive"))
      (node (ref "EXT_1") (pin "CPL") (pinfunction "CPL_CPL") (pintype "bidirectional"))
    )
    (net (code "123") (name "Net-(CP3-Pad2)") (class "Default")
      (node (ref "CP3") (pin "2") (pinfunction "2_2") (pintype "passive"))
      (node (ref "EXT_1") (pin "CPH") (pinfunction "CPH_CPH") (pintype "bidirectional"))
    )
    (net (code "124") (name "Net-(CP4-Pad1)") (class "Default")
      (node (ref "CP4") (pin "1") (pinfunction "1_1") (pintype "passive"))
      (node (ref "EXT_2") (pin "CPL") (pinfunction "CPL_CPL") (pintype "bidirectional"))
    )
    (net (code "125") (name "Net-(CP4-Pad2)") (class "Default")
      (node (ref "CP4") (pin "2") (pinfunction "2_2") (pintype "passive"))
      (node (ref "EXT_2") (pin "CPH") (pinfunction "CPH_CPH") (pintype "bidirectional"))
    )
    (net (code "126") (name "Net-(CPO0-Pad1)") (class "Default")
      (node (ref "CPO0") (pin "1") (pinfunction "1_1") (pintype "passive"))
      (node (ref "X_AXIS") (pin "VCP") (pinfunction "VCP_VCP") (pintype "bidirectional"))
    )
    (net (code "127") (name "Net-(CPO1-Pad1)") (class "Default")
      (node (ref "CPO1") (pin "1") (pinfunction "1_1") (pintype "passive"))
      (node (ref "Y-AXIS") (pin "VCP") (pinfunction "VCP_VCP") (pintype "bidirectional"))
    )
    (net (code "128") (name "Net-(CPO2-Pad1)") (class "Default")
      (node (ref "CPO2") (pin "1") (pinfunction "1_1") (pintype "passive"))
      (node (ref "Z_AXIS") (pin "VCP") (pinfunction "VCP_VCP") (pintype "bidirectional"))
    )
    (net (code "129") (name "Net-(CPO3-Pad1)") (class "Default")
      (node (ref "CPO3") (pin "1") (pinfunction "1_1") (pintype "passive"))
      (node (ref "EXT_1") (pin "VCP") (pinfunction "VCP_VCP") (pintype "bidirectional"))
    )
    (net (code "130") (name "Net-(CPO4-Pad1)") (class "Default")
      (node (ref "CPO4") (pin "1") (pinfunction "1_1") (pintype "passive"))
      (node (ref "EXT_2") (pin "VCP") (pinfunction "VCP_VCP") (pintype "bidirectional"))
    )
    (net (code "131") (name "Net-(C_HOTBA-KL)") (class "Default")
      (node (ref "C_HOTB") (pin "1") (pinfunction "KL_1") (pintype "passive"))
      (node (ref "HOTBED") (pin "3") (pinfunction "D_3") (pintype "passive"))
      (node (ref "HOTBED1") (pin "D") (pinfunction "D_D") (pintype "bidirectional"))
    )
    (net (code "132") (name "Net-(DBC0-Pad1)") (class "Default")
      (node (ref "DBC0") (pin "1") (pinfunction "1_1") (pintype "passive"))
      (node (ref "DBR0") (pin "1") (pinfunction "1_1") (pintype "passive"))
      (node (ref "E2_THERM") (pin "1") (pinfunction "1_1") (pintype "passive"))
    )
    (net (code "133") (name "Net-(DBC1-Pad1)") (class "Default")
      (node (ref "DBC1") (pin "1") (pinfunction "1_1") (pintype "passive"))
      (node (ref "DBR1") (pin "1") (pinfunction "1_1") (pintype "passive"))
      (node (ref "E1_THERM") (pin "1") (pinfunction "1_1") (pintype "passive"))
    )
    (net (code "134") (name "Net-(E1-Pad1)") (class "Default")
      (node (ref "E1") (pin "1") (pinfunction "1_1") (pintype "passive"))
      (node (ref "EXT_1") (pin "AOUT1") (pinfunction "AOUT1_AOUT1") (pintype "bidirectional"))
    )
    (net (code "135") (name "Net-(E1-Pad2)") (class "Default")
      (node (ref "E1") (pin "2") (pinfunction "2_2") (pintype "passive"))
      (node (ref "EXT_1") (pin "AOUT2") (pinfunction "AOUT2_AOUT2") (pintype "bidirectional"))
    )
    (net (code "136") (name "Net-(E2-Pad1)") (class "Default")
      (node (ref "E2") (pin "1") (pinfunction "1_1") (pintype "passive"))
      (node (ref "EXT_2") (pin "AOUT1") (pinfunction "AOUT1_AOUT1") (pintype "bidirectional"))
    )
    (net (code "137") (name "Net-(E2-Pad2)") (class "Default")
      (node (ref "E2") (pin "2") (pinfunction "2_2") (pintype "passive"))
      (node (ref "EXT_2") (pin "AOUT2") (pinfunction "AOUT2_AOUT2") (pintype "bidirectional"))
    )
    (net (code "138") (name "Net-(EXT_1-PadVREF)") (class "Default")
      (node (ref "EXT_1") (pin "VREF") (pinfunction "VREF_VREF") (pintype "bidirectional"))
      (node (ref "RVREF3") (pin "2") (pinfunction "2_2") (pintype "passive"))
      (node (ref "T3") (pin "3") (pinfunction "3_3") (pintype "bidirectional"))
    )
    (net (code "139") (name "Net-(EXT_2-PadVREF)") (class "Default")
      (node (ref "EXT_2") (pin "VREF") (pinfunction "VREF_VREF") (pintype "bidirectional"))
      (node (ref "RVREF4") (pin "2") (pinfunction "2_2") (pintype "passive"))
      (node (ref "T4") (pin "3") (pinfunction "3_3") (pintype "bidirectional"))
    )
    (net (code "140") (name "Net-(FANCA-KL)") (class "Default")
      (node (ref "FANC") (pin "1") (pinfunction "KL_1") (pintype "passive"))
      (node (ref "MOS_FAN") (pin "3") (pinfunction "D_3") (pintype "passive"))
      (node (ref "MOS_FAN1") (pin "D") (pinfunction "D_D") (pintype "bidirectional"))
    )
    (net (code "141") (name "Net-(HOTE2A-KL)") (class "Default")
      (node (ref "HOTE2") (pin "1") (pinfunction "KL_1") (pintype "passive"))
      (node (ref "MOS11") (pin "D") (pinfunction "D_D") (pintype "bidirectional"))
      (node (ref "MOS_1") (pin "3") (pinfunction "D_3") (pintype "passive"))
    )
    (net (code "142") (name "Net-(HOTEA-KL)") (class "Default")
      (node (ref "HOTE") (pin "1") (pinfunction "KL_1") (pintype "passive"))
      (node (ref "HOTEND") (pin "3") (pinfunction "D_3") (pintype "passive"))
      (node (ref "HOTEND1") (pin "D") (pinfunction "D_D") (pintype "bidirectional"))
    )
    (net (code "143") (name "Net-(IC1-AREF)") (class "Default")
      (node (ref "CDECREF1") (pin "2") (pinfunction "2_2") (pintype "passive"))
      (node (ref "IC1") (pin "29") (pinfunction "AREF_29") (pintype "passive"))
    )
    (net (code "144") (name "Net-(IC1-XTAL1)") (class "Default")
      (node (ref "C_Q2") (pin "2") (pinfunction "2_2") (pintype "passive"))
      (node (ref "IC1") (pin "8") (pinfunction "XTAL1_8") (pintype "bidirectional"))
      (node (ref "X1") (pin "X2") (pinfunction "X2_X2") (pintype "passive"))
    )
    (net (code "145") (name "Net-(IC1-XTAL2)") (class "Default")
      (node (ref "C_Q1") (pin "1") (pinfunction "1_1") (pintype "passive"))
      (node (ref "IC1") (pin "7") (pinfunction "XTAL2_7") (pintype "bidirectional"))
      (node (ref "X1") (pin "X1") (pinfunction "X1_X1") (pintype "passive"))
    )
    (net (code "146") (name "Net-(MOSA-KL)") (class "Default")
      (node (ref "MOS") (pin "1") (pinfunction "KL_1") (pintype "passive"))
      (node (ref "MOS22") (pin "D") (pinfunction "D_D") (pintype "bidirectional"))
      (node (ref "MOS_2") (pin "3") (pinfunction "D_3") (pintype "passive"))
    )
    (net (code "147") (name "Net-(MOT_X-Pad1)") (class "Default")
      (node (ref "MOT_X") (pin "1") (pinfunction "1_1") (pintype "passive"))
      (node (ref "X_AXIS") (pin "AOUT1") (pinfunction "AOUT1_AOUT1") (pintype "bidirectional"))
    )
    (net (code "148") (name "Net-(MOT_X-Pad2)") (class "Default")
      (node (ref "MOT_X") (pin "2") (pinfunction "2_2") (pintype "passive"))
      (node (ref "X_AXIS") (pin "AOUT2") (pinfunction "AOUT2_AOUT2") (pintype "bidirectional"))
    )
    (net (code "149") (name "Net-(MOT_Y-Pad1)") (class "Default")
      (node (ref "MOT_Y") (pin "1") (pinfunction "1_1") (pintype "passive"))
      (node (ref "Y-AXIS") (pin "AOUT1") (pinfunction "AOUT1_AOUT1") (pintype "bidirectional"))
    )
    (net (code "150") (name "Net-(MOT_Y-Pad2)") (class "Default")
      (node (ref "MOT_Y") (pin "2") (pinfunction "2_2") (pintype "passive"))
      (node (ref "Y-AXIS") (pin "AOUT2") (pinfunction "AOUT2_AOUT2") (pintype "bidirectional"))
    )
    (net (code "151") (name "Net-(MOT_Z-Pad5)") (class "Default")
      (node (ref "MOT_Z") (pin "5") (pinfunction "5_5") (pintype "passive"))
      (node (ref "MOT_Z") (pin "6") (pinfunction "6_6") (pintype "passive"))
      (node (ref "Z_AXIS") (pin "AOUT2") (pinfunction "AOUT2_AOUT2") (pintype "bidirectional"))
    )
    (net (code "152") (name "Net-(MOT_Z-Pad7)") (class "Default")
      (node (ref "MOT_Z") (pin "7") (pinfunction "7_7") (pintype "passive"))
      (node (ref "MOT_Z") (pin "8") (pinfunction "8_8") (pintype "passive"))
      (node (ref "Z_AXIS") (pin "AOUT1") (pinfunction "AOUT1_AOUT1") (pintype "bidirectional"))
    )
    (net (code "153") (name "Net-(RVREF0-Pad2)") (class "Default")
      (node (ref "RVREF0") (pin "2") (pinfunction "2_2") (pintype "passive"))
      (node (ref "T0") (pin "3") (pinfunction "3_3") (pintype "bidirectional"))
      (node (ref "X_AXIS") (pin "VREF") (pinfunction "VREF_VREF") (pintype "bidirectional"))
    )
    (net (code "154") (name "Net-(RVREF1-Pad2)") (class "Default")
      (node (ref "RVREF1") (pin "2") (pinfunction "2_2") (pintype "passive"))
      (node (ref "T1") (pin "3") (pinfunction "3_3") (pintype "bidirectional"))
      (node (ref "Y-AXIS") (pin "VREF") (pinfunction "VREF_VREF") (pintype "bidirectional"))
    )
    (net (code "155") (name "Net-(RVREF2-Pad2)") (class "Default")
      (node (ref "RVREF2") (pin "2") (pinfunction "2_2") (pintype "passive"))
      (node (ref "T2") (pin "3") (pinfunction "3_3") (pintype "bidirectional"))
      (node (ref "Z_AXIS") (pin "VREF") (pinfunction "VREF_VREF") (pintype "bidirectional"))
    )
    (net (code "156") (name "Net-(SUPPLY-BOOT)") (class "Default")
      (node (ref "CB") (pin "1") (pinfunction "1_1") (pintype "passive"))
      (node (ref "SUPPLY") (pin "1") (pinfunction "BOOT_1") (pintype "bidirectional"))
    )
    (net (code "157") (name "Net-(SUPPLY-COMP)") (class "Default")
      (node (ref "CCOMP") (pin "2") (pinfunction "2_2") (pintype "passive"))
      (node (ref "RCOMP") (pin "2") (pinfunction "2_2") (pintype "passive"))
      (node (ref "SUPPLY") (pin "8") (pinfunction "COMP_8") (pintype "bidirectional"))
    )
    (net (code "158") (name "Net-(SUPPLY-EN)") (class "Default")
      (node (ref "REN1") (pin "1") (pinfunction "1_1") (pintype "passive"))
      (node (ref "REN2") (pin "2") (pinfunction "2_2") (pintype "passive"))
      (node (ref "SUPPLY") (pin "3") (pinfunction "EN_3") (pintype "bidirectional"))
    )
    (net (code "159") (name "Net-(SUPPLY-PH)") (class "Default")
      (node (ref "CB") (pin "2") (pinfunction "2_2") (pintype "passive"))
      (node (ref "D1") (pin "C") (pinfunction "C_C") (pintype "passive"))
      (node (ref "L1") (pin "1") (pinfunction "1_1") (pintype "passive"))
      (node (ref "SUPPLY") (pin "10") (pinfunction "PH_10") (pintype "bidirectional"))
    )
    (net (code "160") (name "Net-(SUPPLY-RT{slash}CLK)") (class "Default")
      (node (ref "RRT") (pin "2") (pinfunction "2_2") (pintype "passive"))
      (node (ref "SUPPLY") (pin "5") (pinfunction "RT/CLK_5") (pintype "bidirectional"))
    )
    (net (code "161") (name "Net-(SUPPLY-SS{slash}TR)") (class "Default")
      (node (ref "CSS") (pin "2") (pinfunction "2_2") (pintype "passive"))
      (node (ref "SUPPLY") (pin "4") (pinfunction "SS/TR_4") (pintype "bidirectional"))
    )
    (net (code "162") (name "Net-(SUPPLY-VSENSE)") (class "Default")
      (node (ref "RF1") (pin "1") (pinfunction "1_1") (pintype "passive"))
      (node (ref "RF2") (pin "2") (pinfunction "2_2") (pintype "passive"))
      (node (ref "SUPPLY") (pin "7") (pinfunction "VSENSE_7") (pintype "bidirectional"))
    )
    (net (code "163") (name "Net-(USB-Pad1)") (class "Default")
      (node (ref "USB") (pin "1") (pinfunction "1_1") (pintype "passive"))
      (node (ref "USB1") (pin "1") (pinfunction "1_1") (pintype "passive"))
    )
    (net (code "164") (name "unconnected-(EXT_1-PadNFAULT)") (class "Default")
      (node (ref "EXT_1") (pin "NFAULT") (pinfunction "NFAULT_NFAULT") (pintype "bidirectional"))
    )
    (net (code "165") (name "unconnected-(EXT_2-PadNFAULT)") (class "Default")
      (node (ref "EXT_2") (pin "NFAULT") (pinfunction "NFAULT_NFAULT") (pintype "bidirectional"))
    )
    (net (code "166") (name "unconnected-(FT232-CBUS0-Pad23)") (class "Default")
      (node (ref "FT232") (pin "23") (pinfunction "CBUS0_23") (pintype "bidirectional"))
    )
    (net (code "167") (name "unconnected-(FT232-CBUS1-Pad22)") (class "Default")
      (node (ref "FT232") (pin "22") (pinfunction "CBUS1_22") (pintype "bidirectional"))
    )
    (net (code "168") (name "unconnected-(FT232-CBUS2-Pad13)") (class "Default")
      (node (ref "FT232") (pin "13") (pinfunction "CBUS2_13") (pintype "bidirectional"))
    )
    (net (code "169") (name "unconnected-(FT232-CBUS3-Pad14)") (class "Default")
      (node (ref "FT232") (pin "14") (pinfunction "CBUS3_14") (pintype "bidirectional"))
    )
    (net (code "170") (name "unconnected-(FT232-CBUS4-Pad12)") (class "Default")
      (node (ref "FT232") (pin "12") (pinfunction "CBUS4_12") (pintype "bidirectional"))
    )
    (net (code "171") (name "unconnected-(FT232-OSCI-Pad27)") (class "Default")
      (node (ref "FT232") (pin "27") (pinfunction "OSCI_27") (pintype "input"))
    )
    (net (code "172") (name "unconnected-(FT232-OSCO-Pad28)") (class "Default")
      (node (ref "FT232") (pin "28") (pinfunction "OSCO_28") (pintype "output"))
    )
    (net (code "173") (name "unconnected-(FT232-~{CTS}-Pad11)") (class "Default")
      (node (ref "FT232") (pin "11") (pinfunction "~{CTS}_11") (pintype "input"))
    )
    (net (code "174") (name "unconnected-(FT232-~{DCD}-Pad10)") (class "Default")
      (node (ref "FT232") (pin "10") (pinfunction "~{DCD}_10") (pintype "input"))
    )
    (net (code "175") (name "unconnected-(FT232-~{DSR}-Pad9)") (class "Default")
      (node (ref "FT232") (pin "9") (pinfunction "~{DSR}_9") (pintype "input"))
    )
    (net (code "176") (name "unconnected-(FT232-~{DTR}-Pad2)") (class "Default")
      (node (ref "FT232") (pin "2") (pinfunction "~{DTR}_2") (pintype "output"))
    )
    (net (code "177") (name "unconnected-(FT232-~{RI}-Pad6)") (class "Default")
      (node (ref "FT232") (pin "6") (pinfunction "~{RI}_6") (pintype "input"))
    )
    (net (code "178") (name "unconnected-(FT232-~{RTS}-Pad3)") (class "Default")
      (node (ref "FT232") (pin "3") (pinfunction "~{RTS}_3") (pintype "output"))
    )
    (net (code "179") (name "unconnected-(ISP-Pad5)") (class "Default")
      (node (ref "ISP") (pin "5") (pinfunction "5_5") (pintype "passive"))
    )
    (net (code "180") (name "unconnected-(SD-DATA1-PadDAT1)") (class "Default")
      (node (ref "SD") (pin "DAT1") (pinfunction "DATA1_DAT1") (pintype "bidirectional"))
    )
    (net (code "181") (name "unconnected-(SD-DATA3{slash}CD-PadCD)") (class "Default")
      (node (ref "SD") (pin "CD") (pinfunction "DATA3/CD_CD") (pintype "bidirectional"))
    )
    (net (code "182") (name "unconnected-(SD-PadDATA2)") (class "Default")
      (node (ref "SD") (pin "DATA2") (pinfunction "DATA2_DATA2") (pintype "bidirectional"))
    )
    (net (code "183") (name "unconnected-(SD-PadWP)") (class "Default")
      (node (ref "SD") (pin "WP") (pinfunction "WP_WP") (pintype "bidirectional"))
    )
    (net (code "184") (name "unconnected-(SUPPLY-PWRGD-Pad6)") (class "Default")
      (node (ref "SUPPLY") (pin "6") (pinfunction "PWRGD_6") (pintype "bidirectional"))
    )
    (net (code "185") (name "unconnected-(T0-Pad2)") (class "Default")
      (node (ref "T0") (pin "2") (pinfunction "2_2") (pintype "bidirectional"))
    )
    (net (code "186") (name "unconnected-(T1-Pad2)") (class "Default")
      (node (ref "T1") (pin "2") (pinfunction "2_2") (pintype "bidirectional"))
    )
    (net (code "187") (name "unconnected-(T2-Pad2)") (class "Default")
      (node (ref "T2") (pin "2") (pinfunction "2_2") (pintype "bidirectional"))
    )
    (net (code "188") (name "unconnected-(T3-Pad2)") (class "Default")
      (node (ref "T3") (pin "2") (pinfunction "2_2") (pintype "bidirectional"))
    )
    (net (code "189") (name "unconnected-(T4-Pad2)") (class "Default")
      (node (ref "T4") (pin "2") (pinfunction "2_2") (pintype "bidirectional"))
    )
    (net (code "190") (name "unconnected-(USB-S1-PadM1)") (class "Default")
      (node (ref "USB") (pin "M1") (pinfunction "S1_M1") (pintype "passive"))
    )
    (net (code "191") (name "unconnected-(USB-S2-PadM2)") (class "Default")
      (node (ref "USB") (pin "M2") (pinfunction "S2_M2") (pintype "passive"))
    )
    (net (code "192") (name "unconnected-(USD-CARD_DET-PadCD)") (class "Default")
      (node (ref "USD") (pin "CD") (pinfunction "CARD_DET_CD") (pintype "bidirectional"))
    )
    (net (code "193") (name "unconnected-(USD-DAT1_X-Pad8)") (class "Default")
      (node (ref "USD") (pin "8") (pinfunction "DAT1_X_8") (pintype "bidirectional"))
    )
    (net (code "194") (name "unconnected-(USD-DAT2_X-Pad1)") (class "Default")
      (node (ref "USD") (pin "1") (pinfunction "DAT2_X_1") (pintype "bidirectional"))
    )
    (net (code "195") (name "unconnected-(X7A-S-Pad1)") (class "Default")
      (node (ref "X7") (pin "1") (pinfunction "S_1") (pintype "passive"))
    )
    (net (code "196") (name "unconnected-(X_AXIS-PadNFAULT)") (class "Default")
      (node (ref "X_AXIS") (pin "NFAULT") (pinfunction "NFAULT_NFAULT") (pintype "bidirectional"))
    )
    (net (code "197") (name "unconnected-(Y-AXIS-PadNFAULT)") (class "Default")
      (node (ref "Y-AXIS") (pin "NFAULT") (pinfunction "NFAULT_NFAULT") (pintype "bidirectional"))
    )
    (net (code "198") (name "unconnected-(Z_AXIS-PadNFAULT)") (class "Default")
      (node (ref "Z_AXIS") (pin "NFAULT") (pinfunction "NFAULT_NFAULT") (pintype "bidirectional"))
    )
  )
)
